# DAQ_Sch.net
KiCad netlist of a schematic drawn in Altium Designer
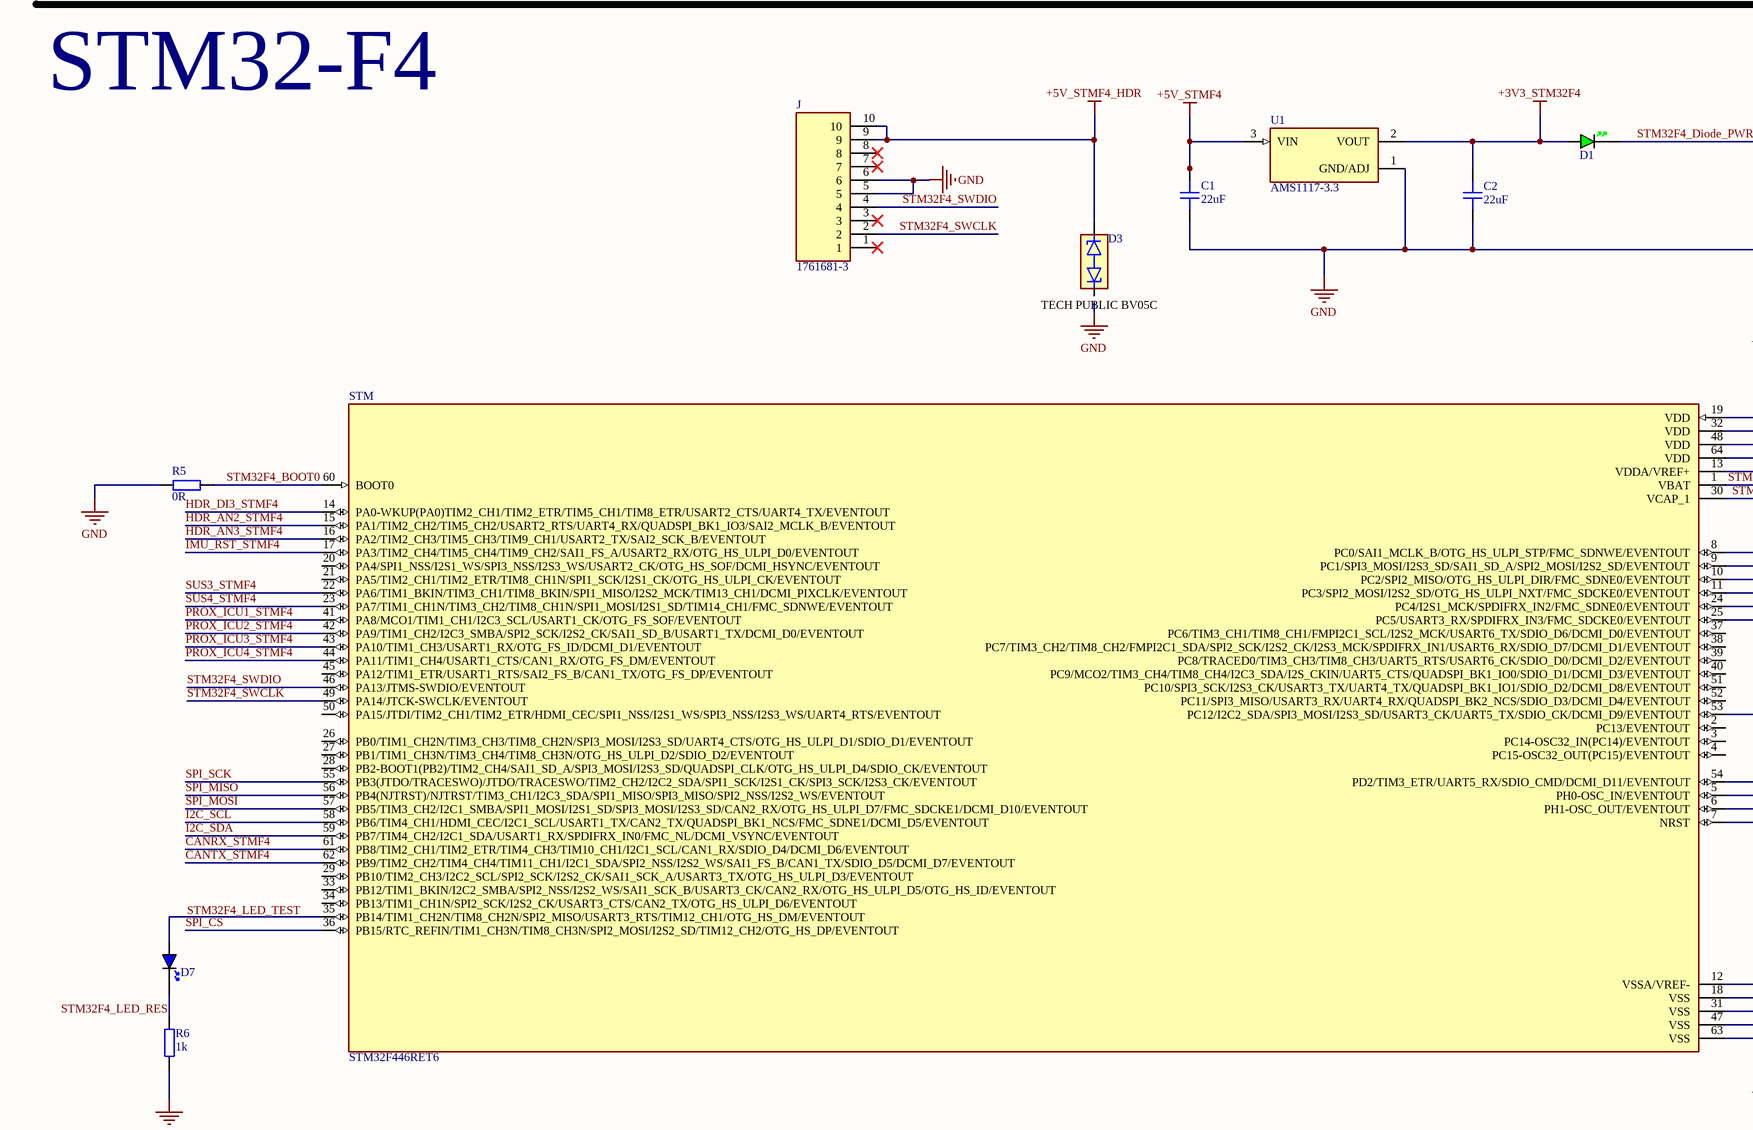
[diagram p0: DAQ_Sch.SchDoc, top left]
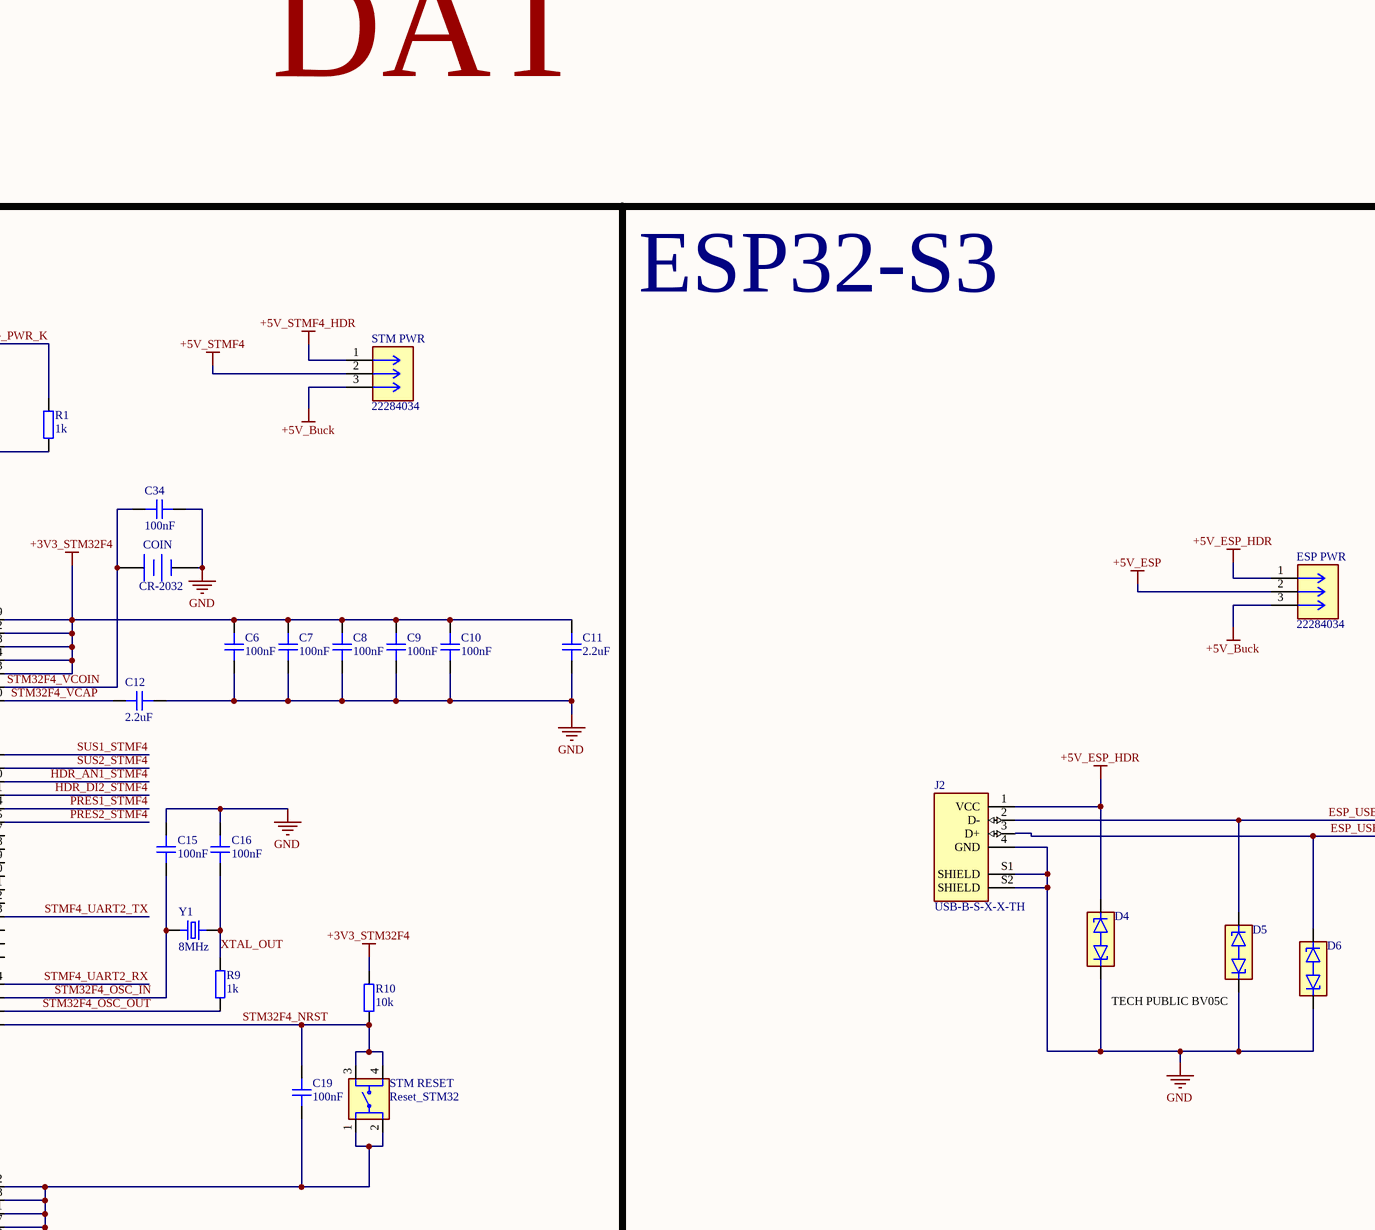
[diagram p1: DAQ_Sch.SchDoc, top middle]
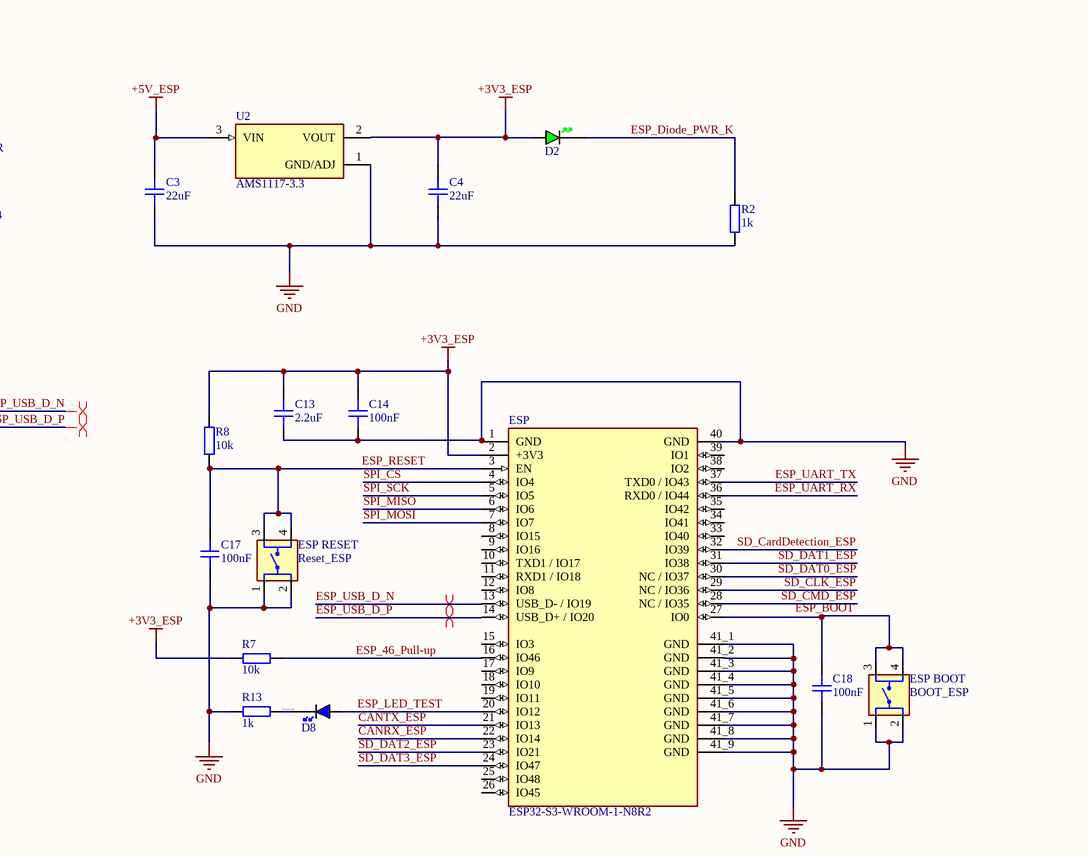
[diagram p2: DAQ_Sch.SchDoc, top right]
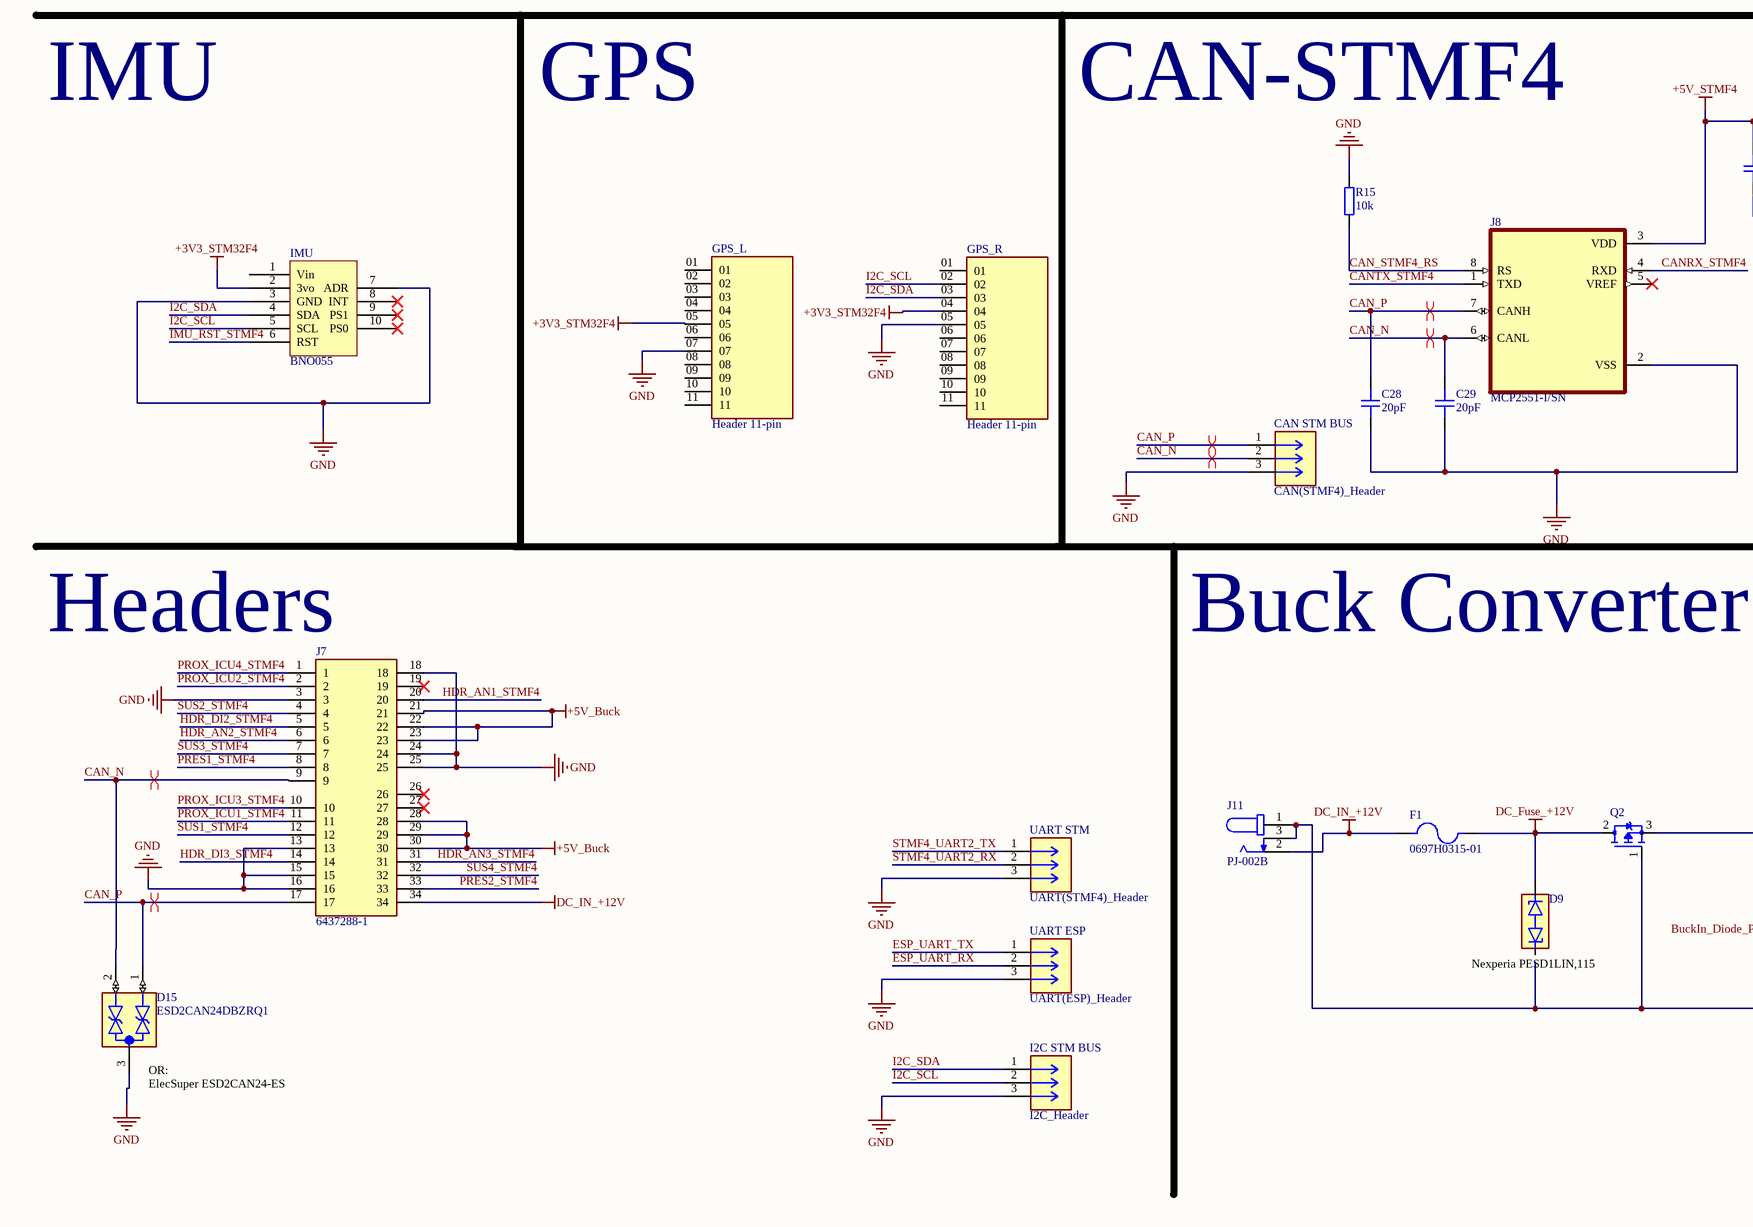
[diagram p3: DAQ_Sch.SchDoc, bottom left]
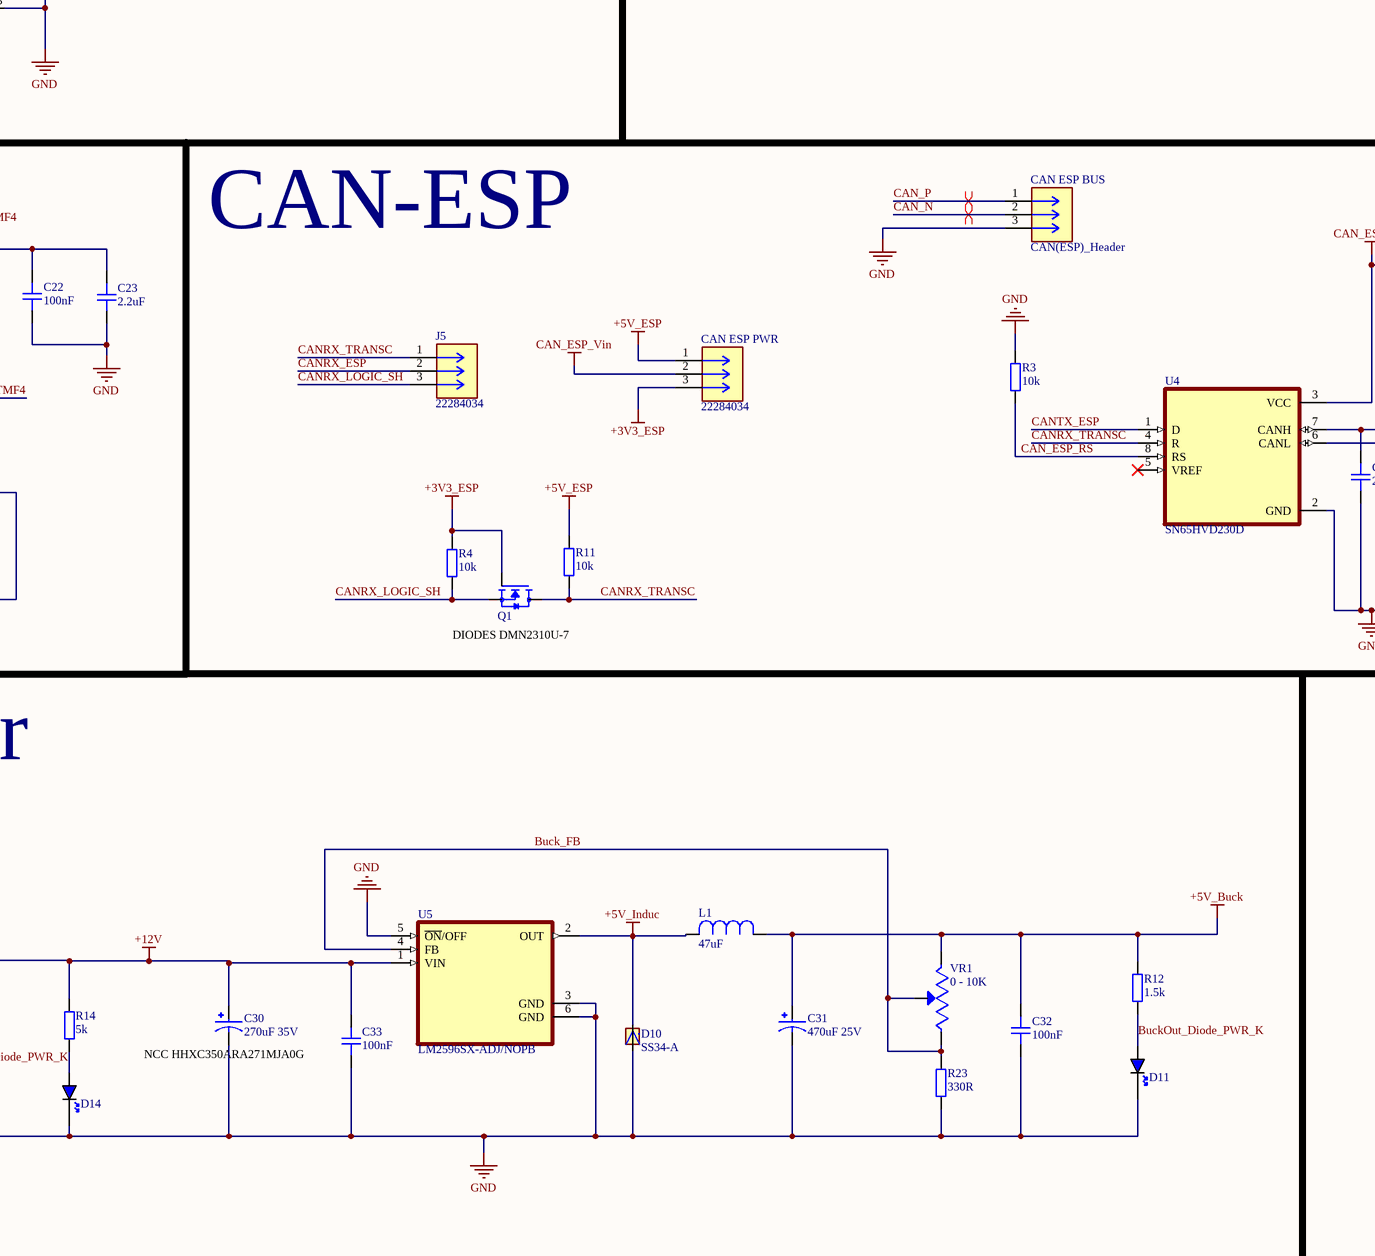
[diagram p4: DAQ_Sch.SchDoc, bottom middle]
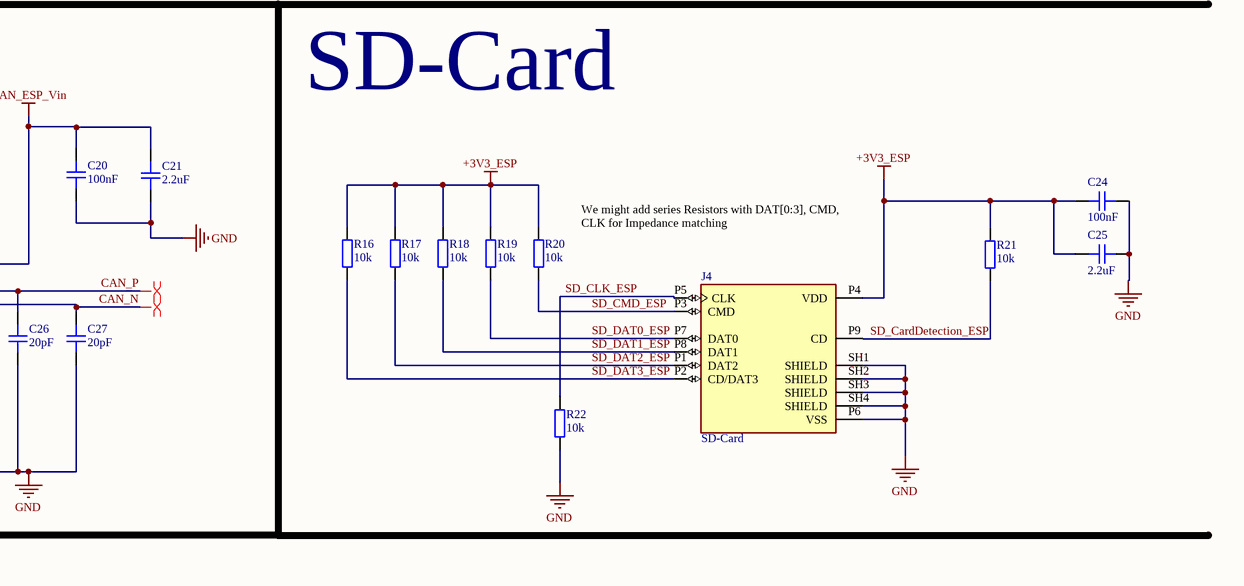
[diagram p5: DAQ_Sch.SchDoc, bottom right]

(export (version "E")
  (design (tool "Eeschema 10.0.6"))
  (components
    (comp (ref "C1")
      (value "22uF")
      (footprint "CAP_0805")
      (description "Capacitor SMD 0805")
      (libsource (lib "Schematic-Lib-PhilsLab") (part "CAP_0805"))
    )
    (comp (ref "C2")
      (value "22uF")
      (footprint "CAP_0805")
      (description "Capacitor SMD 0805")
      (libsource (lib "Schematic-Lib-PhilsLab") (part "CAP_0805"))
    )
    (comp (ref "C3")
      (value "22uF")
      (footprint "CAP_0805")
      (description "Capacitor SMD 0805")
      (libsource (lib "Schematic-Lib-PhilsLab") (part "CAP_0805"))
    )
    (comp (ref "C4")
      (value "22uF")
      (footprint "CAP_0805")
      (description "Capacitor SMD 0805")
      (libsource (lib "Schematic-Lib-PhilsLab") (part "CAP_0805"))
    )
    (comp (ref "C6")
      (value "100nF")
      (footprint "CAP_0805")
      (description "Capacitor SMD 0805")
      (libsource (lib "Schematic-Lib-PhilsLab") (part "CAP_0805"))
    )
    (comp (ref "C7")
      (value "100nF")
      (footprint "CAP_0805")
      (description "Capacitor SMD 0805")
      (libsource (lib "Schematic-Lib-PhilsLab") (part "CAP_0805"))
    )
    (comp (ref "C8")
      (value "100nF")
      (footprint "CAP_0805")
      (description "Capacitor SMD 0805")
      (libsource (lib "Schematic-Lib-PhilsLab") (part "CAP_0805"))
    )
    (comp (ref "C9")
      (value "100nF")
      (footprint "CAP_0805")
      (description "Capacitor SMD 0805")
      (libsource (lib "Schematic-Lib-PhilsLab") (part "CAP_0805"))
    )
    (comp (ref "C10")
      (value "100nF")
      (footprint "CAP_0805")
      (description "Capacitor SMD 0805")
      (libsource (lib "Schematic-Lib-PhilsLab") (part "CAP_0805"))
    )
    (comp (ref "C11")
      (value "2.2uF")
      (footprint "CAP_0805")
      (description "Capacitor SMD 0805")
      (libsource (lib "Schematic-Lib-PhilsLab") (part "CAP_0805"))
    )
    (comp (ref "C12")
      (value "2.2uF")
      (footprint "CAP_0805")
      (description "Capacitor SMD 0805")
      (libsource (lib "Schematic-Lib-PhilsLab") (part "CAP_0805"))
    )
    (comp (ref "C13")
      (value "2.2uF")
      (footprint "CAP_0805")
      (description "Capacitor SMD 0805")
      (libsource (lib "Schematic-Lib-PhilsLab") (part "CAP_0805"))
    )
    (comp (ref "C14")
      (value "100nF")
      (footprint "CAP_0805")
      (description "Capacitor SMD 0805")
      (libsource (lib "Schematic-Lib-PhilsLab") (part "CAP_0805"))
    )
    (comp (ref "C15")
      (value "100nF")
      (footprint "CAP_0805")
      (description "Capacitor SMD 0805")
      (libsource (lib "Schematic-Lib-PhilsLab") (part "CAP_0805"))
    )
    (comp (ref "C16")
      (value "100nF")
      (footprint "CAP_0805")
      (description "Capacitor SMD 0805")
      (libsource (lib "Schematic-Lib-PhilsLab") (part "CAP_0805"))
    )
    (comp (ref "C17")
      (value "100nF")
      (footprint "CAP_0805")
      (description "Capacitor SMD 0805")
      (libsource (lib "Schematic-Lib-PhilsLab") (part "CAP_0805"))
    )
    (comp (ref "C18")
      (value "100nF")
      (footprint "CAP_0805")
      (description "Capacitor SMD 0805")
      (libsource (lib "Schematic-Lib-PhilsLab") (part "CAP_0805"))
    )
    (comp (ref "C19")
      (value "100nF")
      (footprint "CAP_0805")
      (description "Capacitor SMD 0805")
      (libsource (lib "Schematic-Lib-PhilsLab") (part "CAP_0805"))
    )
    (comp (ref "C20")
      (value "100nF")
      (footprint "CAP_0805")
      (description "Capacitor SMD 0805")
      (libsource (lib "Schematic-Lib-PhilsLab") (part "CAP_0805"))
    )
    (comp (ref "C21")
      (value "2.2uF")
      (footprint "CAP_0805")
      (description "Capacitor SMD 0805")
      (libsource (lib "Schematic-Lib-PhilsLab") (part "CAP_0805"))
    )
    (comp (ref "C22")
      (value "100nF")
      (footprint "CAP_0805")
      (description "Capacitor SMD 0805")
      (libsource (lib "Schematic-Lib-PhilsLab") (part "CAP_0805"))
    )
    (comp (ref "C23")
      (value "2.2uF")
      (footprint "CAP_0805")
      (description "Capacitor SMD 0805")
      (libsource (lib "Schematic-Lib-PhilsLab") (part "CAP_0805"))
    )
    (comp (ref "C24")
      (value "100nF")
      (footprint "CAP_0805")
      (description "Capacitor SMD 0805")
      (libsource (lib "Schematic-Lib-PhilsLab") (part "CAP_0805"))
    )
    (comp (ref "C25")
      (value "2.2uF")
      (footprint "CAP_0805")
      (description "Capacitor SMD 0805")
      (libsource (lib "Schematic-Lib-PhilsLab") (part "CAP_0805"))
    )
    (comp (ref "C26")
      (value "20pF")
      (footprint "CAP_0805")
      (description "Capacitor SMD 0805")
      (libsource (lib "Schematic-Lib-PhilsLab") (part "CAP_0805"))
    )
    (comp (ref "C27")
      (value "20pF")
      (footprint "CAP_0805")
      (description "Capacitor SMD 0805")
      (libsource (lib "Schematic-Lib-PhilsLab") (part "CAP_0805"))
    )
    (comp (ref "C28")
      (value "20pF")
      (footprint "CAP_0805")
      (description "Capacitor SMD 0805")
      (libsource (lib "Schematic-Lib-PhilsLab") (part "CAP_0805"))
    )
    (comp (ref "C29")
      (value "20pF")
      (footprint "CAP_0805")
      (description "Capacitor SMD 0805")
      (libsource (lib "Schematic-Lib-PhilsLab") (part "CAP_0805"))
    )
    (comp (ref "C30")
      (value "270uF 35V")
      (footprint "CAP_EEEFT1E471AP")
      (description "35V ±20% 270uF SMD,D10xL10mm Hybrid Aluminum Electrolytic Capacitors ROHS")
      (fields (field (name "MF") "Panasonic") (field (name "MP") "EEEFT1E471AP"))
      (libsource (lib "CAP_EEEFT1E471AP_Sch") (part "EEEFT1E471AP"))
    )
    (comp (ref "C31")
      (value "470uF 25V")
      (footprint "CAP_EEEFT1E471AP")
      (description "Cap Aluminum Lytic 470uF 25V 20% (8 X 10.2mm) SMD 0.08 Ohm 850mA 2000h 105C Automotive T/R")
      (fields (field (name "MF") "Panasonic") (field (name "MP") "EEEFT1E471AP"))
      (libsource (lib "CAP_EEEFT1E471AP_Sch") (part "EEEFT1E471AP"))
    )
    (comp (ref "C32")
      (value "100nF")
      (footprint "CAP_0805")
      (description "Capacitor SMD 0805")
      (libsource (lib "Schematic-Lib-PhilsLab") (part "CAP_0805"))
    )
    (comp (ref "C33")
      (value "100nF")
      (footprint "CAP_0805")
      (description "Capacitor SMD 0805")
      (libsource (lib "Schematic-Lib-PhilsLab") (part "CAP_0805"))
    )
    (comp (ref "C34")
      (value "100nF")
      (footprint "CAP_0805")
      (description "Capacitor SMD 0805")
      (libsource (lib "Schematic-Lib-PhilsLab") (part "CAP_0805"))
    )
    (comp (ref "CAN ESP BUS")
      (value "CAN(ESP)_Header")
      (footprint "CONN_SD-42375-001_M320_03_MOL")
      (fields (field (name "MP") "22284034"))
      (libsource (lib "3_pin_Header_Sch") (part "22284034"))
    )
    (comp (ref "CAN ESP PWR")
      (value "22284034")
      (footprint "CONN_SD-42375-001_M320_03_MOL")
      (libsource (lib "3_pin_Header_Sch") (part "22284034"))
    )
    (comp (ref "CAN STM BUS")
      (value "CAN(STMF4)_Header")
      (footprint "CONN_SD-42375-001_M320_03_MOL")
      (fields (field (name "MP") "22284034"))
      (libsource (lib "3_pin_Header_Sch") (part "22284034"))
    )
    (comp (ref "COIN")
      (value "CR-2032")
      (footprint "PANA-CR-2032HFN")
      (description "Coin Cell Battery, 225 mAh, 0.2 mA, 3 V, -30 to 60 degC, Bulk")
      (fields (field (name "MANUFACTURER") "Panasonic"))
      (libsource (lib "Altium Content Vault") (part "BATTERY_SINGLE-2"))
    )
    (comp (ref "D1")
      (value "GREEN")
      (footprint "LED_0805_GREEN")
      (description "LED 0805 GREEN SMD")
      (libsource (lib "Schematic-Lib-PhilsLab") (part "LED_0805_GREEN"))
    )
    (comp (ref "D2")
      (value "GREEN")
      (footprint "LED_0805_GREEN")
      (description "LED 0805 GREEN SMD")
      (libsource (lib "Schematic-Lib-PhilsLab") (part "LED_0805_GREEN"))
    )
    (comp (ref "D3")
      (value "5V-TVS")
      (footprint "DIO_PESD1LIN")
      (description "10A 8V Bidirectional 5V SOD-323 ESD and Surge Protection (TVS/ESD) ROHS")
      (fields (field (name "MF") "Nexperia USA") (field (name "MP") "PESD1LIN"))
      (libsource (lib "5V_TVS_Diode_Sch") (part "PESD1LIN"))
    )
    (comp (ref "D4")
      (value "5V-TVS")
      (footprint "DIO_PESD1LIN")
      (description "10A 8V Bidirectional 5V SOD-323 ESD and Surge Protection (TVS/ESD) ROHS")
      (fields (field (name "MF") "Nexperia USA") (field (name "MP") "PESD1LIN"))
      (libsource (lib "5V_TVS_Diode_Sch") (part "PESD1LIN"))
    )
    (comp (ref "D5")
      (value "5V-TVS")
      (footprint "DIO_PESD1LIN")
      (description "10A 8V Bidirectional 5V SOD-323 ESD and Surge Protection (TVS/ESD) ROHS")
      (fields (field (name "MF") "Nexperia USA") (field (name "MP") "PESD1LIN"))
      (libsource (lib "5V_TVS_Diode_Sch") (part "PESD1LIN"))
    )
    (comp (ref "D6")
      (value "5V-TVS")
      (footprint "DIO_PESD1LIN")
      (description "10A 8V Bidirectional 5V SOD-323 ESD and Surge Protection (TVS/ESD) ROHS")
      (fields (field (name "MF") "Nexperia USA") (field (name "MP") "PESD1LIN"))
      (libsource (lib "5V_TVS_Diode_Sch") (part "PESD1LIN"))
    )
    (comp (ref "D7")
      (value "BLUE")
      (footprint "LED_0805_BLUE")
      (description "LED 0805 BLUE SMD")
      (libsource (lib "Schematic-Lib-PhilsLab") (part "LED_0805_BLUE"))
    )
    (comp (ref "D8")
      (value "BLUE")
      (footprint "LED_0805_BLUE")
      (description "LED 0805 BLUE SMD")
      (libsource (lib "Schematic-Lib-PhilsLab") (part "LED_0805_BLUE"))
    )
    (comp (ref "D9")
      (value "5V-TVS")
      (footprint "DIO_PESD1LIN")
      (description "44V, 70V Clamp 3A (8/20Âµs) Ipp Tvs Diode Surface Mount SOD-323")
      (fields (field (name "MF") "Nexperia USA") (field (name "MP") "PESD1LIN"))
      (libsource (lib "5V_TVS_Diode_Sch") (part "PESD1LIN"))
    )
    (comp (ref "D10")
      (value "SS34-A")
      (footprint "DO-214AC")
      (description "Schottky barrier diode, 3A, 40V")
      (fields (field (name "MF") "hy electronic corp") (field (name "MP") "SS34A"))
      (libsource (lib "Buck_CatchDiode_SS34-A_Sch") (part "SS34-A"))
    )
    (comp (ref "D11")
      (value "BLUE")
      (footprint "LED_0805_BLUE")
      (description "LED 0805 BLUE SMD")
      (libsource (lib "Schematic-Lib-PhilsLab") (part "LED_0805_BLUE"))
    )
    (comp (ref "D14")
      (value "BLUE")
      (footprint "LED_0805_BLUE")
      (description "LED 0805 BLUE SMD")
      (libsource (lib "Schematic-Lib-PhilsLab") (part "LED_0805_BLUE"))
    )
    (comp (ref "D15")
      (value "ESD2CAN24DBZRQ1")
      (footprint "SOT95P237X112-3N")
      (description "Automotive, dual, 3-pF, ±24-V, ±30-kV ESD protection diode for in-vehicle networks")
      (fields (field (name "MF") "Texas Instruments"))
      (libsource (lib "ESD_CAN_Sch") (part "ESD2CAN24DBZRQ1"))
    )
    (comp (ref "ESP")
      (value "ESP32-S3-WROOM-1-N8R2")
      (footprint "ESP32-S3-WROOM-1_NO-KEEPOUT")
      (fields
        (field (name "MPN") "ESP32-S3-WROOM-1-N16R2")
        (field (name "MF") "Espressif Systems")
        (field (name "DIGI-KEY_PART_NUMBER") "1965-ESP32-S3-WROOM-1-N16R2TR-ND")
      )
      (libsource (lib "ESP32-S3-WROOM-1") (part "ESP32-S3-WROOM-1"))
    )
    (comp (ref "ESP BOOT")
      (value "BOOT_ESP")
      (footprint "SW_FSM8JH")
      (description "Tactile Switch SPST-NO Top Actuated Through Hole")
      (fields (field (name "MP") "FSM8JH") (field (name "MF") "TE Connectivity"))
      (libsource (lib "Button_Sch") (part "FSM8JH"))
    )
    (comp (ref "ESP PWR")
      (value "22284034")
      (footprint "CONN_SD-42375-001_M320_03_MOL")
      (libsource (lib "3_pin_Header_Sch") (part "22284034"))
    )
    (comp (ref "ESP RESET")
      (value "Reset_ESP")
      (footprint "SW_FSM8JH")
      (description "Tactile Switch SPST-NO Top Actuated Through Hole")
      (fields (field (name "MP") "FSM8JH") (field (name "MF") "TE Connectivity"))
      (libsource (lib "Button_Sch") (part "FSM8JH"))
    )
    (comp (ref "F1")
      (value "0697H0315-01")
      (footprint "FUSRR508W60L835T400H810")
      (description "2-Pin Radial Fuse ¦ Rectangular ¦ Slow Blow ¦ UL ¦ 315mA")
      (fields (field (name "MF") "Bel Fuse"))
      (libsource (lib "Radial_Fuse_Sch") (part "0697H0315-01"))
    )
    (comp (ref "GPS_L")
      (value "Header 11-pin")
      (footprint "SAMTEC_MTSW-111-22-T-S-440")
      (fields (field (name "MP") "MTSW-111-22-T-S-440"))
      (libsource (lib "11-pin_Header_Sch") (part "MTSW-111-22-T-S-440"))
    )
    (comp (ref "GPS_R")
      (value "Header 11-pin")
      (footprint "SAMTEC_MTSW-111-22-T-S-440")
      (fields (field (name "MP") "MTSW-111-22-T-S-440"))
      (libsource (lib "11-pin_Header_Sch") (part "MTSW-111-22-T-S-440"))
    )
    (comp (ref "I2C STM BUS")
      (value "I2C_Header")
      (footprint "CONN_SD-42375-001_M320_03_MOL")
      (fields (field (name "MP") "22284034"))
      (libsource (lib "3_pin_Header_Sch") (part "22284034"))
    )
    (comp (ref "IMU") (value "BNO055") (footprint "IMU") (libsource (lib "BNO055") (part "Component_1")))
    (comp (ref "J")
      (value "1761681-3")
      (footprint "TE_1761681-3")
      (description "Conn Shrouded Header HDR 10 POS 2.54mm Solder ST Thru-Hole Tray")
      (fields (field (name "MF") "TE Connectivity"))
      (libsource (lib "10_pin_Box_Header_Sch") (part "1761681-3"))
    )
    (comp (ref "J2")
      (value "USB-B-S-X-X-TH")
      (footprint "SAMTEC_USB-B-S-X-X-TH")
      (description "USB-B (USB TYPE-B) USB 2.0 Receptacle Connector 4 Position Through Hole, Right Angle")
      (fields (field (name "MF") "Samtec") (field (name "MP") "USB-B-S-F-W-TH-TR"))
      (libsource (lib "USB-B_Connector_Sch") (part "USB-B-S-X-X-TH"))
    )
    (comp (ref "J4")
      (value "SD-Card")
      (footprint "GCT_MEM2075-00-140-01-A")
      (description "9 (8 + 1) Position Card Connector microSD Surface Mount, Right Angle Gold")
      (fields (field (name "MF") "Global Connector Technology") (field (name "MP") "MEM2075-00-140-01-A"))
      (libsource (lib "SD-Card_Reader_Sch") (part "MEM2075-00-140-01-A"))
    )
    (comp (ref "J5")
      (value "22284034")
      (footprint "CONN_SD-42375-001_M320_03_MOL")
      (libsource (lib "3_pin_Header_Sch") (part "22284034"))
    )
    (comp (ref "J7")
      (value "6437288-1")
      (footprint "TE_6437288-1")
      (fields (field (name "MF") "TE Connectivity"))
      (libsource (lib "34-pin_Connector_Sch") (part "6437288-1"))
    )
    (comp (ref "J8")
      (value "MCP2551-I/SN")
      (footprint "MCP2551-I_SN_Pcb:SOIC127P599X175-8N")
      (libsource (lib "MCP2551-I_SN_Sch") (part "MCP2551-I/SN"))
    )
    (comp (ref "J11")
      (value "PJ-002B")
      (footprint "CUI_PJ-002B")
      (description "2.5 x 6.5 mm, 2.5 A, Horizontal, Through Hole, Dc Power Jack Connector")
      (fields (field (name "MF") "Same Sky"))
      (libsource (lib "DC_Barrel_Jack_Sch") (part "PJ-002B"))
    )
    (comp (ref "L1")
      (value "47uF")
      (footprint "IND_CDRH127/LDNP-470MC_SUM")
      (description "Inductor Power Shielded Drum Core 47uH 20% 1KHz Ferrite 4.1A 0.078Ohm DCR T/R")
      (fields (field (name "MF") "Sumida Corporation") (field (name "MP") "CDRH127/LDNP-470MC"))
      (libsource (lib "CDRH127_LDNP-470MC") (part "CDRH127/LDNP-470MC"))
    )
    (comp (ref "Q1")
      (value "2N7002")
      (footprint "TRANS_2N7002")
      (description "MOSFET, SOT-23, N, 60V, 0.28A, 5â„¦, 150Â°C")
      (fields (field (name "MF") "Diotec Semiconductor"))
      (libsource (lib "N-MOSFET_SOT23_Sch") (part "2N7002"))
    )
    (comp (ref "Q2")
      (value "IRF4905STRRPBF")
      (footprint "TRANS_IRF4905STRRPBF")
      (fields (field (name "MF") "Infineon Technologies"))
      (libsource (lib "P-MOSFIT_IRF4905STRRPBF_Sch") (part "IRF4905STRRPBF"))
    )
    (comp (ref "R1")
      (value "1k")
      (footprint "RES_0805")
      (description "Resistor SMD 0805")
      (libsource (lib "Schematic-Lib-PhilsLab") (part "RES_0805"))
    )
    (comp (ref "R2")
      (value "1k")
      (footprint "RES_0805")
      (description "Resistor SMD 0805")
      (libsource (lib "Schematic-Lib-PhilsLab") (part "RES_0805"))
    )
    (comp (ref "R3")
      (value "10k")
      (footprint "RES_0805")
      (description "Resistor SMD 0805")
      (libsource (lib "Schematic-Lib-PhilsLab") (part "RES_0805"))
    )
    (comp (ref "R4")
      (value "10k")
      (footprint "RES_0805")
      (description "Resistor SMD 0805")
      (libsource (lib "Schematic-Lib-PhilsLab") (part "RES_0805"))
    )
    (comp (ref "R5")
      (value "0R")
      (footprint "RES_0805")
      (description "Resistor SMD 0805")
      (libsource (lib "Schematic-Lib-PhilsLab") (part "RES_0805"))
    )
    (comp (ref "R6")
      (value "1k")
      (footprint "RES_0805")
      (description "Resistor SMD 0805")
      (libsource (lib "Schematic-Lib-PhilsLab") (part "RES_0805"))
    )
    (comp (ref "R7")
      (value "10k")
      (footprint "RES_0805")
      (description "Resistor SMD 0805")
      (libsource (lib "Schematic-Lib-PhilsLab") (part "RES_0805"))
    )
    (comp (ref "R8")
      (value "10k")
      (footprint "RES_0805")
      (description "Resistor SMD 0805")
      (libsource (lib "Schematic-Lib-PhilsLab") (part "RES_0805"))
    )
    (comp (ref "R9")
      (value "1k")
      (footprint "RES_0805")
      (description "Resistor SMD 0805")
      (libsource (lib "Schematic-Lib-PhilsLab") (part "RES_0805"))
    )
    (comp (ref "R10")
      (value "10k")
      (footprint "RES_0805")
      (description "Resistor SMD 0805")
      (libsource (lib "Schematic-Lib-PhilsLab") (part "RES_0805"))
    )
    (comp (ref "R11")
      (value "10k")
      (footprint "RES_0805")
      (description "Resistor SMD 0805")
      (libsource (lib "Schematic-Lib-PhilsLab") (part "RES_0805"))
    )
    (comp (ref "R12")
      (value "1.5k")
      (footprint "RES_0805")
      (description "Resistor SMD 0805")
      (libsource (lib "Schematic-Lib-PhilsLab") (part "RES_0805"))
    )
    (comp (ref "R13")
      (value "1k")
      (footprint "RES_0805")
      (description "Resistor SMD 0805")
      (libsource (lib "Schematic-Lib-PhilsLab") (part "RES_0805"))
    )
    (comp (ref "R14")
      (value "5k")
      (footprint "RES_0805")
      (description "Resistor SMD 0805")
      (libsource (lib "Schematic-Lib-PhilsLab") (part "RES_0805"))
    )
    (comp (ref "R15")
      (value "10k")
      (footprint "RES_0805")
      (description "Resistor SMD 0805")
      (libsource (lib "Schematic-Lib-PhilsLab") (part "RES_0805"))
    )
    (comp (ref "R16")
      (value "10k")
      (footprint "RES_0805")
      (description "Resistor SMD 0805")
      (libsource (lib "Schematic-Lib-PhilsLab") (part "RES_0805"))
    )
    (comp (ref "R17")
      (value "10k")
      (footprint "RES_0805")
      (description "Resistor SMD 0805")
      (libsource (lib "Schematic-Lib-PhilsLab") (part "RES_0805"))
    )
    (comp (ref "R18")
      (value "10k")
      (footprint "RES_0805")
      (description "Resistor SMD 0805")
      (libsource (lib "Schematic-Lib-PhilsLab") (part "RES_0805"))
    )
    (comp (ref "R19")
      (value "10k")
      (footprint "RES_0805")
      (description "Resistor SMD 0805")
      (libsource (lib "Schematic-Lib-PhilsLab") (part "RES_0805"))
    )
    (comp (ref "R20")
      (value "10k")
      (footprint "RES_0805")
      (description "Resistor SMD 0805")
      (libsource (lib "Schematic-Lib-PhilsLab") (part "RES_0805"))
    )
    (comp (ref "R21")
      (value "10k")
      (footprint "RES_0805")
      (description "Resistor SMD 0805")
      (libsource (lib "Schematic-Lib-PhilsLab") (part "RES_0805"))
    )
    (comp (ref "R22")
      (value "10k")
      (footprint "RES_0805")
      (description "Resistor SMD 0805")
      (libsource (lib "Schematic-Lib-PhilsLab") (part "RES_0805"))
    )
    (comp (ref "R23")
      (value "330R")
      (footprint "RES_0805")
      (description "Resistor SMD 0805")
      (libsource (lib "Schematic-Lib-PhilsLab") (part "RES_0805"))
    )
    (comp (ref "STM")
      (value "STM32F446RET6")
      (footprint "QFP50P1200X1200X160-64N")
      (description "ARMÂ® CortexÂ®-M4 STM32F4 Microcontroller IC 32-Bit 180MHz 512KB _512K x 8_ FLASH 64-LQFP _10x10_")
      (fields (field (name "MF") "STMicroelectronics"))
      (libsource (lib "STM32F4_Sch") (part "STM32F446RET6"))
    )
    (comp (ref "STM PWR")
      (value "22284034")
      (footprint "CONN_SD-42375-001_M320_03_MOL")
      (libsource (lib "3_pin_Header_Sch") (part "22284034"))
    )
    (comp (ref "STM RESET")
      (value "Reset_STM32")
      (footprint "SW_FSM8JH")
      (description "Tactile Switch SPST-NO Top Actuated Through Hole")
      (fields (field (name "MP") "FSM8JH") (field (name "MF") "TE Connectivity"))
      (libsource (lib "Button_Sch") (part "FSM8JH"))
    )
    (comp (ref "U1")
      (value "AMS1117-3.3")
      (footprint "SOT229P700X180-4N")
      (description "Sot223/Pkg 1-Amp 3.3-Volt Low Drop Out Voltage Regulatator")
      (fields (field (name "MF") "Advanced Monolithic Systems"))
      (libsource (lib "AMS1117-3.3_Sch") (part "AMS1117-3.3"))
    )
    (comp (ref "U2")
      (value "AMS1117-3.3")
      (footprint "SOT229P700X180-4N")
      (description "Sot223/Pkg 1-Amp 3.3-Volt Low Drop Out Voltage Regulatator")
      (fields (field (name "MF") "Advanced Monolithic Systems"))
      (libsource (lib "AMS1117-3.3_Sch") (part "AMS1117-3.3"))
    )
    (comp (ref "U4")
      (value "SN65HVD230D")
      (footprint "SOIC127P599X175-8N")
      (description "3.3 V CAN Transceiver with Standby Mode")
      (fields (field (name "MF") "Texas Instruments"))
      (libsource (lib "SN65HVD230D_CAN3.3V_Sch") (part "SN65HVD230D"))
    )
    (comp (ref "U5")
      (value "LM2596SX-ADJ/NOPB")
      (footprint "VREG_LM2596SX-ADJ/NOPB")
      (fields (field (name "MF") "Texas Instruments"))
      (libsource (lib "LM2596SX-ADJ_NOPB_Sch") (part "LM2596SX-ADJ/NOPB"))
    )
    (comp (ref "UART ESP")
      (value "UART(ESP)_Header")
      (footprint "CONN_SD-42375-001_M320_03_MOL")
      (fields (field (name "MP") "22284034"))
      (libsource (lib "3_pin_Header_Sch") (part "22284034"))
    )
    (comp (ref "UART STM")
      (value "UART(STMF4)_Header")
      (footprint "CONN_SD-42375-001_M320_03_MOL")
      (fields (field (name "MP") "22284034"))
      (libsource (lib "3_pin_Header_Sch") (part "22284034"))
    )
    (comp (ref "VR1")
      (value "0 - 10K")
      (footprint "TRIM_3296W-1-103LF")
      (description "Trimmer, Cermet, Rest 10 Kilohms, PCB, 25 Turns, Pwr-Rtg 0.5W, 3296 Series ¦ Bourns 3296W-1-103LF")
      (fields (field (name "MF") "Bourns") (field (name "MP") "3296W-1-103LF"))
      (libsource (lib "Pot_10KOhm_Sch") (part "3296W-1-103LF"))
    )
    (comp (ref "Y1")
      (value "8MHz")
      (footprint "XTAL_ECS-80-20-5PVX")
      (description "SMD Quartz crystal")
      (fields (field (name "MP") "ECS-80-20-5PVX"))
      (libsource (lib "Crystal_8MHz_20pF_Sch") (part "ECS-80-20-5PVX"))
    )
  )
  (nets
    (net (code "1") (name "+3V3_ESP") (class "Default")
      (node (ref "C13") (pin "1") (pinfunction "1_1") (pintype "passive"))
      (node (ref "C14") (pin "1") (pinfunction "1_1") (pintype "passive"))
      (node (ref "C24") (pin "2") (pinfunction "2_2") (pintype "passive"))
      (node (ref "C25") (pin "2") (pinfunction "2_2") (pintype "passive"))
      (node (ref "C4") (pin "2") (pinfunction "2_2") (pintype "passive"))
      (node (ref "CAN ESP PWR") (pin "3") (pinfunction "3_3") (pintype "passive"))
      (node (ref "D2") (pin "A") (pinfunction "A_A") (pintype "passive"))
      (node (ref "ESP") (pin "2") (pinfunction "+3V3_2") (pintype "power_in"))
      (node (ref "J4") (pin "P4") (pinfunction "VDD_P4") (pintype "power_in"))
      (node (ref "Q1") (pin "1") (pinfunction "G_1") (pintype "passive"))
      (node (ref "R16") (pin "2") (pinfunction "2_2") (pintype "passive"))
      (node (ref "R17") (pin "2") (pinfunction "2_2") (pintype "passive"))
      (node (ref "R18") (pin "2") (pinfunction "2_2") (pintype "passive"))
      (node (ref "R19") (pin "2") (pinfunction "2_2") (pintype "passive"))
      (node (ref "R20") (pin "2") (pinfunction "2_2") (pintype "passive"))
      (node (ref "R21") (pin "2") (pinfunction "2_2") (pintype "passive"))
      (node (ref "R4") (pin "2") (pinfunction "2_2") (pintype "passive"))
      (node (ref "R7") (pin "1") (pinfunction "1_1") (pintype "passive"))
      (node (ref "R8") (pin "2") (pinfunction "2_2") (pintype "passive"))
      (node (ref "U2") (pin "2") (pinfunction "VOUT_2") (pintype "power_in"))
    )
    (net (code "2") (name "+3V3_STM32F4") (class "Default")
      (node (ref "C10") (pin "2") (pinfunction "2_2") (pintype "passive"))
      (node (ref "C11") (pin "2") (pinfunction "2_2") (pintype "passive"))
      (node (ref "C2") (pin "2") (pinfunction "2_2") (pintype "passive"))
      (node (ref "C6") (pin "2") (pinfunction "2_2") (pintype "passive"))
      (node (ref "C7") (pin "2") (pinfunction "2_2") (pintype "passive"))
      (node (ref "C8") (pin "2") (pinfunction "2_2") (pintype "passive"))
      (node (ref "C9") (pin "2") (pinfunction "2_2") (pintype "passive"))
      (node (ref "D1") (pin "A") (pinfunction "A_A") (pintype "passive"))
      (node (ref "GPS_L") (pin "05") (pinfunction "05_05") (pintype "passive"))
      (node (ref "GPS_R") (pin "04") (pinfunction "04_04") (pintype "passive"))
      (node (ref "IMU") (pin "2") (pinfunction "3vo_2") (pintype "passive"))
      (node (ref "R10") (pin "2") (pinfunction "2_2") (pintype "passive"))
      (node (ref "STM") (pin "13") (pinfunction "VDDA/VREF+_13") (pintype "power_in"))
      (node (ref "STM") (pin "19") (pinfunction "VDD_19") (pintype "input"))
      (node (ref "STM") (pin "32") (pinfunction "VDD_32") (pintype "power_in"))
      (node (ref "STM") (pin "48") (pinfunction "VDD_48") (pintype "power_in"))
      (node (ref "STM") (pin "64") (pinfunction "VDD_64") (pintype "power_in"))
      (node (ref "U1") (pin "2") (pinfunction "VOUT_2") (pintype "power_in"))
    )
    (net (code "3") (name "+5V_Buck") (class "Default")
      (node (ref "C31") (pin "1") (pinfunction "1_1") (pintype "passive"))
      (node (ref "C32") (pin "2") (pinfunction "2_2") (pintype "passive"))
      (node (ref "ESP PWR") (pin "3") (pinfunction "3_3") (pintype "passive"))
      (node (ref "J7") (pin "21") (pinfunction "21_21") (pintype "passive"))
      (node (ref "J7") (pin "22") (pinfunction "22_22") (pintype "passive"))
      (node (ref "J7") (pin "23") (pinfunction "23_23") (pintype "passive"))
      (node (ref "J7") (pin "28") (pinfunction "28_28") (pintype "passive"))
      (node (ref "J7") (pin "29") (pinfunction "29_29") (pintype "passive"))
      (node (ref "J7") (pin "30") (pinfunction "30_30") (pintype "passive"))
      (node (ref "L1") (pin "1") (pinfunction "1_1") (pintype "passive"))
      (node (ref "R12") (pin "2") (pinfunction "2_2") (pintype "passive"))
      (node (ref "STM PWR") (pin "3") (pinfunction "3_3") (pintype "passive"))
      (node (ref "VR1") (pin "3") (pinfunction "CW_3") (pintype "passive"))
    )
    (net (code "4") (name "+5V_ESP") (class "Default")
      (node (ref "C3") (pin "2") (pinfunction "2_2") (pintype "passive"))
      (node (ref "CAN ESP PWR") (pin "1") (pinfunction "1_1") (pintype "passive"))
      (node (ref "ESP PWR") (pin "2") (pinfunction "2_2") (pintype "passive"))
      (node (ref "R11") (pin "2") (pinfunction "2_2") (pintype "passive"))
      (node (ref "U2") (pin "3") (pinfunction "VIN_3") (pintype "input"))
    )
    (net (code "5") (name "+5V_ESP_HDR") (class "Default")
      (node (ref "D4") (pin "2") (pinfunction "2_2") (pintype "passive"))
      (node (ref "ESP PWR") (pin "1") (pinfunction "1_1") (pintype "passive"))
      (node (ref "J2") (pin "1") (pinfunction "VCC_1") (pintype "power_in"))
    )
    (net (code "6") (name "+5V_Induc") (class "Default")
      (node (ref "D10") (pin "C") (pinfunction "C_C") (pintype "passive"))
      (node (ref "L1") (pin "2") (pinfunction "2_2") (pintype "passive"))
      (node (ref "U5") (pin "2") (pinfunction "OUT_2") (pintype "output"))
    )
    (net (code "7") (name "+5V_STMF4") (class "Default")
      (node (ref "C1") (pin "2") (pinfunction "2_2") (pintype "passive"))
      (node (ref "C22") (pin "2") (pinfunction "2_2") (pintype "passive"))
      (node (ref "C23") (pin "2") (pinfunction "2_2") (pintype "passive"))
      (node (ref "J8") (pin "3") (pinfunction "VDD_3") (pintype "power_in"))
      (node (ref "STM PWR") (pin "2") (pinfunction "2_2") (pintype "passive"))
      (node (ref "U1") (pin "3") (pinfunction "VIN_3") (pintype "input"))
    )
    (net (code "8") (name "+5V_STMF4_HDR") (class "Default")
      (node (ref "D3") (pin "2") (pinfunction "2_2") (pintype "passive"))
      (node (ref "J") (pin "10") (pinfunction "10_10") (pintype "passive"))
      (node (ref "J") (pin "9") (pinfunction "9_9") (pintype "passive"))
      (node (ref "STM PWR") (pin "1") (pinfunction "1_1") (pintype "passive"))
    )
    (net (code "9") (name "+12V") (class "Default")
      (node (ref "C30") (pin "1") (pinfunction "1_1") (pintype "passive"))
      (node (ref "C33") (pin "2") (pinfunction "2_2") (pintype "passive"))
      (node (ref "Q2") (pin "3") (pinfunction "S_3") (pintype "passive"))
      (node (ref "R14") (pin "2") (pinfunction "2_2") (pintype "passive"))
      (node (ref "U5") (pin "1") (pinfunction "VIN_1") (pintype "input"))
    )
    (net (code "10") (name "/BuckIn_Diode_PWR_K") (class "Default")
      (node (ref "D14") (pin "A") (pinfunction "A_A") (pintype "passive"))
      (node (ref "R14") (pin "1") (pinfunction "1_1") (pintype "passive"))
    )
    (net (code "11") (name "/BuckOut_Diode_PWR_K") (class "Default")
      (node (ref "D11") (pin "A") (pinfunction "A_A") (pintype "passive"))
      (node (ref "R12") (pin "1") (pinfunction "1_1") (pintype "passive"))
    )
    (net (code "12") (name "/Buck_FB") (class "Default")
      (node (ref "R23") (pin "2") (pinfunction "2_2") (pintype "passive"))
      (node (ref "U5") (pin "4") (pinfunction "FB_4") (pintype "input"))
      (node (ref "VR1") (pin "1") (pinfunction "CCW_1") (pintype "passive"))
      (node (ref "VR1") (pin "2") (pinfunction "WIPER_2") (pintype "passive"))
    )
    (net (code "13") (name "/CANRX_ESP") (class "Default")
      (node (ref "ESP") (pin "22") (pinfunction "IO14_22") (pintype "bidirectional"))
      (node (ref "J5") (pin "2") (pinfunction "2_2") (pintype "passive"))
    )
    (net (code "14") (name "/CANRX_LOGIC_SH") (class "Default")
      (node (ref "J5") (pin "3") (pinfunction "3_3") (pintype "passive"))
      (node (ref "Q1") (pin "2") (pinfunction "S_2") (pintype "passive"))
      (node (ref "R4") (pin "1") (pinfunction "1_1") (pintype "passive"))
    )
    (net (code "15") (name "/CANRX_STMF4") (class "Default")
      (node (ref "J8") (pin "4") (pinfunction "RXD_4") (pintype "input"))
      (node (ref "STM") (pin "61") (pinfunction "PB8/TIM2_CH1/TIM2_ETR/TIM4_CH3/TIM10_CH1/I2C1_SCL/CAN1_RX/SDIO_D4/DCMI_D6/EVENTOUT_61") (pintype "bidirectional"))
    )
    (net (code "16") (name "/CANRX_TRANSC") (class "Default")
      (node (ref "J5") (pin "1") (pinfunction "1_1") (pintype "passive"))
      (node (ref "Q1") (pin "3") (pinfunction "D_3") (pintype "passive"))
      (node (ref "R11") (pin "1") (pinfunction "1_1") (pintype "passive"))
      (node (ref "U4") (pin "4") (pinfunction "R_4") (pintype "input"))
    )
    (net (code "17") (name "/CANTX_ESP") (class "Default")
      (node (ref "ESP") (pin "21") (pinfunction "IO13_21") (pintype "bidirectional"))
      (node (ref "U4") (pin "1") (pinfunction "D_1") (pintype "input"))
    )
    (net (code "18") (name "/CANTX_STMF4") (class "Default")
      (node (ref "J8") (pin "1") (pinfunction "TXD_1") (pintype "input"))
      (node (ref "STM") (pin "62") (pinfunction "PB9/TIM2_CH2/TIM4_CH4/TIM11_CH1/I2C1_SDA/SPI2_NSS/I2S2_WS/SAI1_FS_B/CAN1_TX/SDIO_D5/DCMI_D7/EVENTOUT_62") (pintype "bidirectional"))
    )
    (net (code "19") (name "/CAN_ESP_RS") (class "Default")
      (node (ref "R3") (pin "1") (pinfunction "1_1") (pintype "passive"))
      (node (ref "U4") (pin "8") (pinfunction "RS_8") (pintype "input"))
    )
    (net (code "20") (name "/CAN_N") (class "Default")
      (node (ref "C27") (pin "2") (pinfunction "2_2") (pintype "passive"))
      (node (ref "C29") (pin "2") (pinfunction "2_2") (pintype "passive"))
      (node (ref "CAN ESP BUS") (pin "2") (pinfunction "2_2") (pintype "passive"))
      (node (ref "CAN STM BUS") (pin "2") (pinfunction "2_2") (pintype "passive"))
      (node (ref "D15") (pin "2") (pinfunction "IO2_2") (pintype "bidirectional"))
      (node (ref "J7") (pin "9") (pinfunction "9_9") (pintype "passive"))
      (node (ref "J8") (pin "6") (pinfunction "CANL_6") (pintype "bidirectional"))
      (node (ref "U4") (pin "6") (pinfunction "CANL_6") (pintype "bidirectional"))
    )
    (net (code "21") (name "/CAN_P") (class "Default")
      (node (ref "C26") (pin "2") (pinfunction "2_2") (pintype "passive"))
      (node (ref "C28") (pin "2") (pinfunction "2_2") (pintype "passive"))
      (node (ref "CAN ESP BUS") (pin "1") (pinfunction "1_1") (pintype "passive"))
      (node (ref "CAN STM BUS") (pin "1") (pinfunction "1_1") (pintype "passive"))
      (node (ref "D15") (pin "1") (pinfunction "IO1_1") (pintype "bidirectional"))
      (node (ref "J7") (pin "17") (pinfunction "17_17") (pintype "passive"))
      (node (ref "J8") (pin "7") (pinfunction "CANH_7") (pintype "bidirectional"))
      (node (ref "U4") (pin "7") (pinfunction "CANH_7") (pintype "bidirectional"))
    )
    (net (code "22") (name "/CAN_STMF4_RS") (class "Default")
      (node (ref "J8") (pin "8") (pinfunction "RS_8") (pintype "input"))
      (node (ref "R15") (pin "1") (pinfunction "1_1") (pintype "passive"))
    )
    (net (code "23") (name "/ESP_46_Pull-up") (class "Default")
      (node (ref "ESP") (pin "16") (pinfunction "IO46_16") (pintype "bidirectional"))
      (node (ref "R7") (pin "2") (pinfunction "2_2") (pintype "passive"))
    )
    (net (code "24") (name "/ESP_BOOT") (class "Default")
      (node (ref "C18") (pin "1") (pinfunction "1_1") (pintype "passive"))
      (node (ref "ESP") (pin "27") (pinfunction "IO0_27") (pintype "bidirectional"))
      (node (ref "ESP BOOT") (pin "3") (pinfunction "3_3") (pintype "passive"))
      (node (ref "ESP BOOT") (pin "4") (pinfunction "4_4") (pintype "passive"))
    )
    (net (code "25") (name "/ESP_Diode_PWR_K") (class "Default")
      (node (ref "D2") (pin "K") (pinfunction "K_K") (pintype "passive"))
      (node (ref "R2") (pin "1") (pinfunction "1_1") (pintype "passive"))
    )
    (net (code "26") (name "/ESP_LED_RES") (class "Default")
      (node (ref "D8") (pin "K") (pinfunction "K_K") (pintype "passive"))
      (node (ref "R13") (pin "1") (pinfunction "1_1") (pintype "passive"))
    )
    (net (code "28") (name "/ESP_LED_TEST") (class "Default")
      (node (ref "D8") (pin "A") (pinfunction "A_A") (pintype "passive"))
      (node (ref "ESP") (pin "20") (pinfunction "IO12_20") (pintype "bidirectional"))
    )
    (net (code "29") (name "/ESP_RESET") (class "Default")
      (node (ref "C17") (pin "1") (pinfunction "1_1") (pintype "passive"))
      (node (ref "ESP") (pin "3") (pinfunction "EN_3") (pintype "input"))
      (node (ref "ESP RESET") (pin "3") (pinfunction "3_3") (pintype "passive"))
      (node (ref "ESP RESET") (pin "4") (pinfunction "4_4") (pintype "passive"))
      (node (ref "R8") (pin "1") (pinfunction "1_1") (pintype "passive"))
    )
    (net (code "30") (name "/ESP_UART_RX") (class "Default")
      (node (ref "ESP") (pin "36") (pinfunction "RXD0_/_IO44_36") (pintype "bidirectional"))
      (node (ref "UART ESP") (pin "2") (pinfunction "2_2") (pintype "passive"))
    )
    (net (code "31") (name "/ESP_UART_TX") (class "Default")
      (node (ref "ESP") (pin "37") (pinfunction "TXD0_/_IO43_37") (pintype "bidirectional"))
      (node (ref "UART ESP") (pin "1") (pinfunction "1_1") (pintype "passive"))
    )
    (net (code "32") (name "/ESP_USB_D_N") (class "Default")
      (node (ref "D5") (pin "2") (pinfunction "2_2") (pintype "passive"))
      (node (ref "ESP") (pin "13") (pinfunction "USB_D-_/_IO19_13") (pintype "bidirectional"))
      (node (ref "J2") (pin "2") (pinfunction "D-_2") (pintype "bidirectional"))
    )
    (net (code "33") (name "/ESP_USB_D_P") (class "Default")
      (node (ref "D6") (pin "2") (pinfunction "2_2") (pintype "passive"))
      (node (ref "ESP") (pin "14") (pinfunction "USB_D+_/_IO20_14") (pintype "bidirectional"))
      (node (ref "J2") (pin "3") (pinfunction "D+_3") (pintype "bidirectional"))
    )
    (net (code "34") (name "/HDR_AN1_STMF4") (class "Default")
      (node (ref "J7") (pin "20") (pinfunction "20_20") (pintype "passive"))
      (node (ref "STM") (pin "10") (pinfunction "PC2/SPI2_MISO/OTG_HS_ULPI_DIR/FMC_SDNE0/EVENTOUT_10") (pintype "bidirectional"))
    )
    (net (code "35") (name "/HDR_AN2_STMF4") (class "Default")
      (node (ref "J7") (pin "6") (pinfunction "6_6") (pintype "passive"))
      (node (ref "STM") (pin "15") (pinfunction "PA1/TIM2_CH2/TIM5_CH2/USART2_RTS/UART4_RX/QUADSPI_BK1_IO3/SAI2_MCLK_B/EVENTOUT_15") (pintype "bidirectional"))
    )
    (net (code "36") (name "/HDR_AN3_STMF4") (class "Default")
      (node (ref "J7") (pin "31") (pinfunction "31_31") (pintype "passive"))
      (node (ref "STM") (pin "16") (pinfunction "PA2/TIM2_CH3/TIM5_CH3/TIM9_CH1/USART2_TX/SAI2_SCK_B/EVENTOUT_16") (pintype "bidirectional"))
    )
    (net (code "37") (name "/HDR_DI2_STMF4") (class "Default")
      (node (ref "J7") (pin "5") (pinfunction "5_5") (pintype "passive"))
      (node (ref "STM") (pin "11") (pinfunction "PC3/SPI2_MOSI/I2S2_SD/OTG_HS_ULPI_NXT/FMC_SDCKE0/EVENTOUT_11") (pintype "bidirectional"))
    )
    (net (code "38") (name "/HDR_DI3_STMF4") (class "Default")
      (node (ref "J7") (pin "14") (pinfunction "14_14") (pintype "passive"))
      (node (ref "STM") (pin "14") (pinfunction "PA0-WKUP(PA0)TIM2_CH1/TIM2_ETR/TIM5_CH1/TIM8_ETR/USART2_CTS/UART4_TX/EVENTOUT_14") (pintype "bidirectional"))
    )
    (net (code "39") (name "/I2C_SCL") (class "Default")
      (node (ref "GPS_R") (pin "02") (pinfunction "02_02") (pintype "passive"))
      (node (ref "I2C STM BUS") (pin "2") (pinfunction "2_2") (pintype "passive"))
      (node (ref "IMU") (pin "5") (pinfunction "SCL_5") (pintype "passive"))
      (node (ref "STM") (pin "58") (pinfunction "PB6/TIM4_CH1/HDMI_CEC/I2C1_SCL/USART1_TX/CAN2_TX/QUADSPI_BK1_NCS/FMC_SDNE1/DCMI_D5/EVENTOUT_58") (pintype "bidirectional"))
    )
    (net (code "40") (name "/I2C_SDA") (class "Default")
      (node (ref "GPS_R") (pin "03") (pinfunction "03_03") (pintype "passive"))
      (node (ref "I2C STM BUS") (pin "1") (pinfunction "1_1") (pintype "passive"))
      (node (ref "IMU") (pin "4") (pinfunction "SDA_4") (pintype "passive"))
      (node (ref "STM") (pin "59") (pinfunction "PB7/TIM4_CH2/I2C1_SDA/USART1_RX/SPDIFRX_IN0/FMC_NL/DCMI_VSYNC/EVENTOUT_59") (pintype "bidirectional"))
    )
    (net (code "41") (name "/IMU_RST_STMF4") (class "Default")
      (node (ref "IMU") (pin "6") (pinfunction "RST_6") (pintype "passive"))
      (node (ref "STM") (pin "17") (pinfunction "PA3/TIM2_CH4/TIM5_CH4/TIM9_CH2/SAI1_FS_A/USART2_RX/OTG_HS_ULPI_D0/EVENTOUT_17") (pintype "bidirectional"))
    )
    (net (code "42") (name "/PRES1_STMF4") (class "Default")
      (node (ref "J7") (pin "8") (pinfunction "8_8") (pintype "passive"))
      (node (ref "STM") (pin "24") (pinfunction "PC4/I2S1_MCK/SPDIFRX_IN2/FMC_SDNE0/EVENTOUT_24") (pintype "bidirectional"))
    )
    (net (code "43") (name "/PRES2_STMF4") (class "Default")
      (node (ref "J7") (pin "33") (pinfunction "33_33") (pintype "passive"))
      (node (ref "STM") (pin "25") (pinfunction "PC5/USART3_RX/SPDIFRX_IN3/FMC_SDCKE0/EVENTOUT_25") (pintype "bidirectional"))
    )
    (net (code "44") (name "/PROX_ICU1_STMF4") (class "Default")
      (node (ref "J7") (pin "11") (pinfunction "11_11") (pintype "passive"))
      (node (ref "STM") (pin "41") (pinfunction "PA8/MCO1/TIM1_CH1/I2C3_SCL/USART1_CK/OTG_FS_SOF/EVENTOUT_41") (pintype "bidirectional"))
    )
    (net (code "45") (name "/PROX_ICU2_STMF4") (class "Default")
      (node (ref "J7") (pin "2") (pinfunction "2_2") (pintype "passive"))
      (node (ref "STM") (pin "42") (pinfunction "PA9/TIM1_CH2/I2C3_SMBA/SPI2_SCK/I2S2_CK/SAI1_SD_B/USART1_TX/DCMI_D0/EVENTOUT_42") (pintype "bidirectional"))
    )
    (net (code "46") (name "/PROX_ICU3_STMF4") (class "Default")
      (node (ref "J7") (pin "10") (pinfunction "10_10") (pintype "passive"))
      (node (ref "STM") (pin "43") (pinfunction "PA10/TIM1_CH3/USART1_RX/OTG_FS_ID/DCMI_D1/EVENTOUT_43") (pintype "bidirectional"))
    )
    (net (code "47") (name "/PROX_ICU4_STMF4") (class "Default")
      (node (ref "J7") (pin "1") (pinfunction "1_1") (pintype "passive"))
      (node (ref "STM") (pin "44") (pinfunction "PA11/TIM1_CH4/USART1_CTS/CAN1_RX/OTG_FS_DM/EVENTOUT_44") (pintype "bidirectional"))
    )
    (net (code "48") (name "/SD_CLK_ESP") (class "Default")
      (node (ref "ESP") (pin "29") (pinfunction "NC_/_IO36_29") (pintype "bidirectional"))
      (node (ref "J4") (pin "P5") (pinfunction "CLK_P5") (pintype "bidirectional"))
      (node (ref "R22") (pin "2") (pinfunction "2_2") (pintype "passive"))
    )
    (net (code "49") (name "/SD_CMD_ESP") (class "Default")
      (node (ref "ESP") (pin "28") (pinfunction "NC_/_IO35_28") (pintype "bidirectional"))
      (node (ref "J4") (pin "P3") (pinfunction "CMD_P3") (pintype "bidirectional"))
      (node (ref "R20") (pin "1") (pinfunction "1_1") (pintype "passive"))
    )
    (net (code "50") (name "/SD_CardDetection_ESP") (class "Default")
      (node (ref "ESP") (pin "32") (pinfunction "IO39_32") (pintype "bidirectional"))
      (node (ref "J4") (pin "P9") (pinfunction "CD_P9") (pintype "passive"))
      (node (ref "R21") (pin "1") (pinfunction "1_1") (pintype "passive"))
    )
    (net (code "51") (name "/SD_DAT0_ESP") (class "Default")
      (node (ref "ESP") (pin "30") (pinfunction "NC_/_IO37_30") (pintype "bidirectional"))
      (node (ref "J4") (pin "P7") (pinfunction "DAT0_P7") (pintype "bidirectional"))
      (node (ref "R19") (pin "1") (pinfunction "1_1") (pintype "passive"))
    )
    (net (code "52") (name "/SD_DAT1_ESP") (class "Default")
      (node (ref "ESP") (pin "31") (pinfunction "IO38_31") (pintype "bidirectional"))
      (node (ref "J4") (pin "P8") (pinfunction "DAT1_P8") (pintype "bidirectional"))
      (node (ref "R18") (pin "1") (pinfunction "1_1") (pintype "passive"))
    )
    (net (code "53") (name "/SD_DAT2_ESP") (class "Default")
      (node (ref "ESP") (pin "23") (pinfunction "IO21_23") (pintype "bidirectional"))
      (node (ref "J4") (pin "P1") (pinfunction "DAT2_P1") (pintype "bidirectional"))
      (node (ref "R17") (pin "1") (pinfunction "1_1") (pintype "passive"))
    )
    (net (code "54") (name "/SD_DAT3_ESP") (class "Default")
      (node (ref "ESP") (pin "24") (pinfunction "IO47_24") (pintype "bidirectional"))
      (node (ref "J4") (pin "P2") (pinfunction "CD/DAT3_P2") (pintype "bidirectional"))
      (node (ref "R16") (pin "1") (pinfunction "1_1") (pintype "passive"))
    )
    (net (code "55") (name "/SPI_CS") (class "Default")
      (node (ref "ESP") (pin "4") (pinfunction "IO4_4") (pintype "bidirectional"))
      (node (ref "STM") (pin "36") (pinfunction "PB15/RTC_REFIN/TIM1_CH3N/TIM8_CH3N/SPI2_MOSI/I2S2_SD/TIM12_CH2/OTG_HS_DP/EVENTOUT_36") (pintype "bidirectional"))
    )
    (net (code "56") (name "/SPI_MISO") (class "Default")
      (node (ref "ESP") (pin "6") (pinfunction "IO6_6") (pintype "bidirectional"))
      (node (ref "STM") (pin "56") (pinfunction "PB4(NJTRST)/NJTRST/TIM3_CH1/I2C3_SDA/SPI1_MISO/SPI3_MISO/SPI2_NSS/I2S2_WS/EVENTOUT_56") (pintype "bidirectional"))
    )
    (net (code "57") (name "/SPI_MOSI") (class "Default")
      (node (ref "ESP") (pin "7") (pinfunction "IO7_7") (pintype "bidirectional"))
      (node (ref "STM") (pin "57") (pinfunction "PB5/TIM3_CH2/I2C1_SMBA/SPI1_MOSI/I2S1_SD/SPI3_MOSI/I2S3_SD/CAN2_RX/OTG_HS_ULPI_D7/FMC_SDCKE1/DCMI_D10/EVENTOUT_57") (pintype "bidirectional"))
    )
    (net (code "58") (name "/SPI_SCK") (class "Default")
      (node (ref "ESP") (pin "5") (pinfunction "IO5_5") (pintype "bidirectional"))
      (node (ref "STM") (pin "55") (pinfunction "PB3(JTDO/TRACESWO)/JTDO/TRACESWO/TIM2_CH2/I2C2_SDA/SPI1_SCK/I2S1_CK/SPI3_SCK/I2S3_CK/EVENTOUT_55") (pintype "bidirectional"))
    )
    (net (code "59") (name "/STM32F4_BOOT0") (class "Default")
      (node (ref "R5") (pin "2") (pinfunction "2_2") (pintype "passive"))
      (node (ref "STM") (pin "60") (pinfunction "BOOT0_60") (pintype "input"))
    )
    (net (code "60") (name "/STM32F4_Diode_PWR_K") (class "Default")
      (node (ref "D1") (pin "K") (pinfunction "K_K") (pintype "passive"))
      (node (ref "R1") (pin "2") (pinfunction "2_2") (pintype "passive"))
    )
    (net (code "62") (name "/STM32F4_LED_RES") (class "Default")
      (node (ref "D7") (pin "K") (pinfunction "K_K") (pintype "passive"))
      (node (ref "R6") (pin "2") (pinfunction "2_2") (pintype "passive"))
    )
    (net (code "63") (name "/STM32F4_NRST") (class "Default")
      (node (ref "C19") (pin "2") (pinfunction "2_2") (pintype "passive"))
      (node (ref "R10") (pin "1") (pinfunction "1_1") (pintype "passive"))
      (node (ref "STM") (pin "7") (pinfunction "NRST_7") (pintype "bidirectional"))
      (node (ref "STM RESET") (pin "3") (pinfunction "3_3") (pintype "passive"))
      (node (ref "STM RESET") (pin "4") (pinfunction "4_4") (pintype "passive"))
    )
    (net (code "64") (name "/STM32F4_OSC_IN") (class "Default")
      (node (ref "C15") (pin "1") (pinfunction "1_1") (pintype "passive"))
      (node (ref "STM") (pin "5") (pinfunction "PH0-OSC_IN/EVENTOUT_5") (pintype "bidirectional"))
      (node (ref "Y1") (pin "2") (pinfunction "2_2") (pintype "passive"))
    )
    (net (code "65") (name "/STM32F4_OSC_OUT") (class "Default")
      (node (ref "R9") (pin "1") (pinfunction "1_1") (pintype "passive"))
      (node (ref "STM") (pin "6") (pinfunction "PH1-OSC_OUT/EVENTOUT_6") (pintype "bidirectional"))
    )
    (net (code "66") (name "/STM32F4_SWCLK") (class "Default")
      (node (ref "J") (pin "2") (pinfunction "2_2") (pintype "passive"))
      (node (ref "STM") (pin "49") (pinfunction "PA14/JTCK-SWCLK/EVENTOUT_49") (pintype "bidirectional"))
    )
    (net (code "67") (name "/STM32F4_SWDIO") (class "Default")
      (node (ref "J") (pin "4") (pinfunction "4_4") (pintype "passive"))
      (node (ref "STM") (pin "46") (pinfunction "PA13/JTMS-SWDIO/EVENTOUT_46") (pintype "bidirectional"))
    )
    (net (code "68") (name "/STM32F4_VCAP") (class "Default")
      (node (ref "C12") (pin "2") (pinfunction "2_2") (pintype "passive"))
      (node (ref "STM") (pin "30") (pinfunction "VCAP_1_30") (pintype "power_in"))
    )
    (net (code "69") (name "/STM32F4_VCOIN") (class "Default")
      (node (ref "C34") (pin "2") (pinfunction "2_2") (pintype "passive"))
      (node (ref "COIN") (pin "1") (pinfunction "+_1") (pintype "passive"))
      (node (ref "STM") (pin "1") (pinfunction "VBAT_1") (pintype "power_in"))
    )
    (net (code "70") (name "/STMF4_UART2_RX") (class "Default")
      (node (ref "STM") (pin "54") (pinfunction "PD2/TIM3_ETR/UART5_RX/SDIO_CMD/DCMI_D11/EVENTOUT_54") (pintype "bidirectional"))
      (node (ref "UART STM") (pin "2") (pinfunction "2_2") (pintype "passive"))
    )
    (net (code "71") (name "/STMF4_UART2_TX") (class "Default")
      (node (ref "STM") (pin "53") (pinfunction "PC12/I2C2_SDA/SPI3_MOSI/I2S3_SD/USART3_CK/UART5_TX/SDIO_CK/DCMI_D9/EVENTOUT_53") (pintype "bidirectional"))
      (node (ref "UART STM") (pin "1") (pinfunction "1_1") (pintype "passive"))
    )
    (net (code "72") (name "/SUS1_STMF4") (class "Default")
      (node (ref "J7") (pin "12") (pinfunction "12_12") (pintype "passive"))
      (node (ref "STM") (pin "8") (pinfunction "PC0/SAI1_MCLK_B/OTG_HS_ULPI_STP/FMC_SDNWE/EVENTOUT_8") (pintype "bidirectional"))
    )
    (net (code "73") (name "/SUS2_STMF4") (class "Default")
      (node (ref "J7") (pin "4") (pinfunction "4_4") (pintype "passive"))
      (node (ref "STM") (pin "9") (pinfunction "PC1/SPI3_MOSI/I2S3_SD/SAI1_SD_A/SPI2_MOSI/I2S2_SD/EVENTOUT_9") (pintype "bidirectional"))
    )
    (net (code "74") (name "/SUS3_STMF4") (class "Default")
      (node (ref "J7") (pin "7") (pinfunction "7_7") (pintype "passive"))
      (node (ref "STM") (pin "22") (pinfunction "PA6/TIM1_BKIN/TIM3_CH1/TIM8_BKIN/SPI1_MISO/I2S2_MCK/TIM13_CH1/DCMI_PIXCLK/EVENTOUT_22") (pintype "bidirectional"))
    )
    (net (code "75") (name "/SUS4_STMF4") (class "Default")
      (node (ref "J7") (pin "32") (pinfunction "32_32") (pintype "passive"))
      (node (ref "STM") (pin "23") (pinfunction "PA7/TIM1_CH1N/TIM3_CH2/TIM8_CH1N/SPI1_MOSI/I2S1_SD/TIM14_CH1/FMC_SDNWE/EVENTOUT_23") (pintype "bidirectional"))
    )
    (net (code "76") (name "/XTAL_OUT") (class "Default")
      (node (ref "C16") (pin "1") (pinfunction "1_1") (pintype "passive"))
      (node (ref "R9") (pin "2") (pinfunction "2_2") (pintype "passive"))
      (node (ref "Y1") (pin "1") (pinfunction "1_1") (pintype "passive"))
    )
    (net (code "77") (name "CAN_ESP_Vin") (class "Default")
      (node (ref "C20") (pin "2") (pinfunction "2_2") (pintype "passive"))
      (node (ref "C21") (pin "2") (pinfunction "2_2") (pintype "passive"))
      (node (ref "CAN ESP PWR") (pin "2") (pinfunction "2_2") (pintype "passive"))
      (node (ref "U4") (pin "3") (pinfunction "VCC_3") (pintype "power_in"))
    )
    (net (code "78") (name "DC_Fuse_+12V") (class "Default")
      (node (ref "D9") (pin "2") (pinfunction "2_2") (pintype "passive"))
      (node (ref "F1") (pin "2") (pinfunction "2_2") (pintype "passive"))
      (node (ref "Q2") (pin "2") (pinfunction "D_2") (pintype "passive"))
    )
    (net (code "79") (name "DC_IN_+12V") (class "Default")
      (node (ref "F1") (pin "1") (pinfunction "1_1") (pintype "passive"))
      (node (ref "J11") (pin "2") (pinfunction "2_2") (pintype "passive"))
      (node (ref "J7") (pin "34") (pinfunction "34_34") (pintype "passive"))
    )
    (net (code "80") (name "GND") (class "Default")
      (node (ref "C1") (pin "1") (pinfunction "1_1") (pintype "passive"))
      (node (ref "C10") (pin "1") (pinfunction "1_1") (pintype "passive"))
      (node (ref "C11") (pin "1") (pinfunction "1_1") (pintype "passive"))
      (node (ref "C12") (pin "1") (pinfunction "1_1") (pintype "passive"))
      (node (ref "C13") (pin "2") (pinfunction "2_2") (pintype "passive"))
      (node (ref "C14") (pin "2") (pinfunction "2_2") (pintype "passive"))
      (node (ref "C15") (pin "2") (pinfunction "2_2") (pintype "passive"))
      (node (ref "C16") (pin "2") (pinfunction "2_2") (pintype "passive"))
      (node (ref "C17") (pin "2") (pinfunction "2_2") (pintype "passive"))
      (node (ref "C18") (pin "2") (pinfunction "2_2") (pintype "passive"))
      (node (ref "C19") (pin "1") (pinfunction "1_1") (pintype "passive"))
      (node (ref "C2") (pin "1") (pinfunction "1_1") (pintype "passive"))
      (node (ref "C20") (pin "1") (pinfunction "1_1") (pintype "passive"))
      (node (ref "C21") (pin "1") (pinfunction "1_1") (pintype "passive"))
      (node (ref "C22") (pin "1") (pinfunction "1_1") (pintype "passive"))
      (node (ref "C23") (pin "1") (pinfunction "1_1") (pintype "passive"))
      (node (ref "C24") (pin "1") (pinfunction "1_1") (pintype "passive"))
      (node (ref "C25") (pin "1") (pinfunction "1_1") (pintype "passive"))
      (node (ref "C26") (pin "1") (pinfunction "1_1") (pintype "passive"))
      (node (ref "C27") (pin "1") (pinfunction "1_1") (pintype "passive"))
      (node (ref "C28") (pin "1") (pinfunction "1_1") (pintype "passive"))
      (node (ref "C29") (pin "1") (pinfunction "1_1") (pintype "passive"))
      (node (ref "C3") (pin "1") (pinfunction "1_1") (pintype "passive"))
      (node (ref "C30") (pin "2") (pinfunction "2_2") (pintype "passive"))
      (node (ref "C31") (pin "2") (pinfunction "2_2") (pintype "passive"))
      (node (ref "C32") (pin "1") (pinfunction "1_1") (pintype "passive"))
      (node (ref "C33") (pin "1") (pinfunction "1_1") (pintype "passive"))
      (node (ref "C34") (pin "1") (pinfunction "1_1") (pintype "passive"))
      (node (ref "C4") (pin "1") (pinfunction "1_1") (pintype "passive"))
      (node (ref "C6") (pin "1") (pinfunction "1_1") (pintype "passive"))
      (node (ref "C7") (pin "1") (pinfunction "1_1") (pintype "passive"))
      (node (ref "C8") (pin "1") (pinfunction "1_1") (pintype "passive"))
      (node (ref "C9") (pin "1") (pinfunction "1_1") (pintype "passive"))
      (node (ref "CAN ESP BUS") (pin "3") (pinfunction "3_3") (pintype "passive"))
      (node (ref "CAN STM BUS") (pin "3") (pinfunction "3_3") (pintype "passive"))
      (node (ref "COIN") (pin "2") (pinfunction "-_2") (pintype "passive"))
      (node (ref "D10") (pin "A") (pinfunction "A_A") (pintype "passive"))
      (node (ref "D11") (pin "K") (pinfunction "K_K") (pintype "passive"))
      (node (ref "D14") (pin "K") (pinfunction "K_K") (pintype "passive"))
      (node (ref "D15") (pin "3") (pinfunction "GND_3") (pintype "power_in"))
      (node (ref "D3") (pin "1") (pinfunction "1_1") (pintype "passive"))
      (node (ref "D4") (pin "1") (pinfunction "1_1") (pintype "passive"))
      (node (ref "D5") (pin "1") (pinfunction "1_1") (pintype "passive"))
      (node (ref "D6") (pin "1") (pinfunction "1_1") (pintype "passive"))
      (node (ref "D9") (pin "1") (pinfunction "1_1") (pintype "passive"))
      (node (ref "ESP") (pin "1") (pinfunction "GND_1") (pintype "power_in"))
      (node (ref "ESP") (pin "40") (pinfunction "GND_40") (pintype "power_in"))
      (node (ref "ESP") (pin "41_1") (pinfunction "GND_41_1") (pintype "power_in"))
      (node (ref "ESP") (pin "41_2") (pinfunction "GND_41_2") (pintype "power_in"))
      (node (ref "ESP") (pin "41_3") (pinfunction "GND_41_3") (pintype "power_in"))
      (node (ref "ESP") (pin "41_4") (pinfunction "GND_41_4") (pintype "power_in"))
      (node (ref "ESP") (pin "41_5") (pinfunction "GND_41_5") (pintype "power_in"))
      (node (ref "ESP") (pin "41_6") (pinfunction "GND_41_6") (pintype "power_in"))
      (node (ref "ESP") (pin "41_7") (pinfunction "GND_41_7") (pintype "power_in"))
      (node (ref "ESP") (pin "41_8") (pinfunction "GND_41_8") (pintype "power_in"))
      (node (ref "ESP") (pin "41_9") (pinfunction "GND_41_9") (pintype "power_in"))
      (node (ref "ESP BOOT") (pin "1") (pinfunction "1_1") (pintype "passive"))
      (node (ref "ESP BOOT") (pin "2") (pinfunction "2_2") (pintype "passive"))
      (node (ref "ESP RESET") (pin "1") (pinfunction "1_1") (pintype "passive"))
      (node (ref "ESP RESET") (pin "2") (pinfunction "2_2") (pintype "passive"))
      (node (ref "GPS_L") (pin "07") (pinfunction "07_07") (pintype "passive"))
      (node (ref "GPS_R") (pin "05") (pinfunction "05_05") (pintype "passive"))
      (node (ref "I2C STM BUS") (pin "3") (pinfunction "3_3") (pintype "passive"))
      (node (ref "IMU") (pin "3") (pinfunction "GND_3") (pintype "passive"))
      (node (ref "IMU") (pin "7") (pinfunction "ADR_7") (pintype "passive"))
      (node (ref "J") (pin "5") (pinfunction "5_5") (pintype "passive"))
      (node (ref "J") (pin "6") (pinfunction "6_6") (pintype "passive"))
      (node (ref "J11") (pin "1") (pinfunction "1_1") (pintype "passive"))
      (node (ref "J11") (pin "3") (pinfunction "3_3") (pintype "passive"))
      (node (ref "J2") (pin "4") (pinfunction "GND_4") (pintype "power_in"))
      (node (ref "J2") (pin "S1") (pinfunction "SHIELD_S1") (pintype "passive"))
      (node (ref "J2") (pin "S2") (pinfunction "SHIELD_S2") (pintype "passive"))
      (node (ref "J4") (pin "P6") (pinfunction "VSS_P6") (pintype "power_in"))
      (node (ref "J4") (pin "SH1") (pinfunction "SHIELD_SH1") (pintype "power_in"))
      (node (ref "J4") (pin "SH2") (pinfunction "SHIELD_SH2") (pintype "power_in"))
      (node (ref "J4") (pin "SH3") (pinfunction "SHIELD_SH3") (pintype "power_in"))
      (node (ref "J4") (pin "SH4") (pinfunction "SHIELD_SH4") (pintype "power_in"))
      (node (ref "J7") (pin "13") (pinfunction "13_13") (pintype "passive"))
      (node (ref "J7") (pin "15") (pinfunction "15_15") (pintype "passive"))
      (node (ref "J7") (pin "16") (pinfunction "16_16") (pintype "passive"))
      (node (ref "J7") (pin "18") (pinfunction "18_18") (pintype "passive"))
      (node (ref "J7") (pin "24") (pinfunction "24_24") (pintype "passive"))
      (node (ref "J7") (pin "25") (pinfunction "25_25") (pintype "passive"))
      (node (ref "J7") (pin "3") (pinfunction "3_3") (pintype "passive"))
      (node (ref "J8") (pin "2") (pinfunction "VSS_2") (pintype "power_in"))
      (node (ref "Q2") (pin "1") (pinfunction "G_1") (pintype "passive"))
      (node (ref "R1") (pin "1") (pinfunction "1_1") (pintype "passive"))
      (node (ref "R13") (pin "2") (pinfunction "2_2") (pintype "passive"))
      (node (ref "R15") (pin "2") (pinfunction "2_2") (pintype "passive"))
      (node (ref "R2") (pin "2") (pinfunction "2_2") (pintype "passive"))
      (node (ref "R22") (pin "1") (pinfunction "1_1") (pintype "passive"))
      (node (ref "R23") (pin "1") (pinfunction "1_1") (pintype "passive"))
      (node (ref "R3") (pin "2") (pinfunction "2_2") (pintype "passive"))
      (node (ref "R5") (pin "1") (pinfunction "1_1") (pintype "passive"))
      (node (ref "R6") (pin "1") (pinfunction "1_1") (pintype "passive"))
      (node (ref "STM") (pin "12") (pinfunction "VSSA/VREF-_12") (pintype "power_in"))
      (node (ref "STM") (pin "18") (pinfunction "VSS_18") (pintype "power_in"))
      (node (ref "STM") (pin "31") (pinfunction "VSS_31") (pintype "power_in"))
      (node (ref "STM") (pin "47") (pinfunction "VSS_47") (pintype "power_in"))
      (node (ref "STM") (pin "63") (pinfunction "VSS_63") (pintype "power_in"))
      (node (ref "STM RESET") (pin "1") (pinfunction "1_1") (pintype "passive"))
      (node (ref "STM RESET") (pin "2") (pinfunction "2_2") (pintype "passive"))
      (node (ref "U1") (pin "1") (pinfunction "GND/ADJ_1") (pintype "power_in"))
      (node (ref "U2") (pin "1") (pinfunction "GND/ADJ_1") (pintype "power_in"))
      (node (ref "U4") (pin "2") (pinfunction "GND_2") (pintype "power_in"))
      (node (ref "U5") (pin "3") (pinfunction "GND_3") (pintype "power_in"))
      (node (ref "U5") (pin "5") (pinfunction "~{ON}/OFF_5") (pintype "input"))
      (node (ref "U5") (pin "6") (pinfunction "GND_6") (pintype "power_in"))
      (node (ref "UART ESP") (pin "3") (pinfunction "3_3") (pintype "passive"))
      (node (ref "UART STM") (pin "3") (pinfunction "3_3") (pintype "passive"))
    )
    (net (code "81") (name "Net-(STM-PB14{slash}TIM1_CH2N{slash}TIM8_CH2N{slash}SPI2_MISO{slash}USART3_RTS{slash}TIM12_CH1{slash}OTG_HS_DM{slash}EVENTOUT)") (class "Default")
      (node (ref "D7") (pin "A") (pinfunction "A_A") (pintype "passive"))
      (node (ref "STM") (pin "35") (pinfunction "PB14/TIM1_CH2N/TIM8_CH2N/SPI2_MISO/USART3_RTS/TIM12_CH1/OTG_HS_DM/EVENTOUT_35") (pintype "bidirectional"))
    )
    (net (code "82") (name "unconnected-(ESP-IO1-Pad39)") (class "Default")
      (node (ref "ESP") (pin "39") (pinfunction "IO1_39") (pintype "bidirectional"))
    )
    (net (code "83") (name "unconnected-(ESP-IO2-Pad38)") (class "Default")
      (node (ref "ESP") (pin "38") (pinfunction "IO2_38") (pintype "bidirectional"))
    )
    (net (code "84") (name "unconnected-(ESP-IO3-Pad15)") (class "Default")
      (node (ref "ESP") (pin "15") (pinfunction "IO3_15") (pintype "bidirectional"))
    )
    (net (code "85") (name "unconnected-(ESP-IO8-Pad12)") (class "Default")
      (node (ref "ESP") (pin "12") (pinfunction "IO8_12") (pintype "bidirectional"))
    )
    (net (code "86") (name "unconnected-(ESP-IO9-Pad17)") (class "Default")
      (node (ref "ESP") (pin "17") (pinfunction "IO9_17") (pintype "bidirectional"))
    )
    (net (code "87") (name "unconnected-(ESP-IO10-Pad18)") (class "Default")
      (node (ref "ESP") (pin "18") (pinfunction "IO10_18") (pintype "bidirectional"))
    )
    (net (code "88") (name "unconnected-(ESP-IO11-Pad19)") (class "Default")
      (node (ref "ESP") (pin "19") (pinfunction "IO11_19") (pintype "bidirectional"))
    )
    (net (code "89") (name "unconnected-(ESP-IO15-Pad8)") (class "Default")
      (node (ref "ESP") (pin "8") (pinfunction "IO15_8") (pintype "bidirectional"))
    )
    (net (code "90") (name "unconnected-(ESP-IO16-Pad9)") (class "Default")
      (node (ref "ESP") (pin "9") (pinfunction "IO16_9") (pintype "bidirectional"))
    )
    (net (code "91") (name "unconnected-(ESP-IO40-Pad33)") (class "Default")
      (node (ref "ESP") (pin "33") (pinfunction "IO40_33") (pintype "bidirectional"))
    )
    (net (code "92") (name "unconnected-(ESP-IO41-Pad34)") (class "Default")
      (node (ref "ESP") (pin "34") (pinfunction "IO41_34") (pintype "bidirectional"))
    )
    (net (code "93") (name "unconnected-(ESP-IO42-Pad35)") (class "Default")
      (node (ref "ESP") (pin "35") (pinfunction "IO42_35") (pintype "bidirectional"))
    )
    (net (code "94") (name "unconnected-(ESP-IO45-Pad26)") (class "Default")
      (node (ref "ESP") (pin "26") (pinfunction "IO45_26") (pintype "bidirectional"))
    )
    (net (code "95") (name "unconnected-(ESP-IO48-Pad25)") (class "Default")
      (node (ref "ESP") (pin "25") (pinfunction "IO48_25") (pintype "bidirectional"))
    )
    (net (code "96") (name "unconnected-(ESP-RXD1_{slash}_IO18-Pad11)") (class "Default")
      (node (ref "ESP") (pin "11") (pinfunction "RXD1_/_IO18_11") (pintype "bidirectional"))
    )
    (net (code "97") (name "unconnected-(ESP-TXD1_{slash}_IO17-Pad10)") (class "Default")
      (node (ref "ESP") (pin "10") (pinfunction "TXD1_/_IO17_10") (pintype "bidirectional"))
    )
    (net (code "98") (name "unconnected-(GPS_L-Pad01)") (class "Default")
      (node (ref "GPS_L") (pin "01") (pinfunction "01_01") (pintype "passive"))
    )
    (net (code "99") (name "unconnected-(GPS_L-Pad02)") (class "Default")
      (node (ref "GPS_L") (pin "02") (pinfunction "02_02") (pintype "passive"))
    )
    (net (code "100") (name "unconnected-(GPS_L-Pad03)") (class "Default")
      (node (ref "GPS_L") (pin "03") (pinfunction "03_03") (pintype "passive"))
    )
    (net (code "101") (name "unconnected-(GPS_L-Pad04)") (class "Default")
      (node (ref "GPS_L") (pin "04") (pinfunction "04_04") (pintype "passive"))
    )
    (net (code "102") (name "unconnected-(GPS_L-Pad06)") (class "Default")
      (node (ref "GPS_L") (pin "06") (pinfunction "06_06") (pintype "passive"))
    )
    (net (code "103") (name "unconnected-(GPS_L-Pad08)") (class "Default")
      (node (ref "GPS_L") (pin "08") (pinfunction "08_08") (pintype "passive"))
    )
    (net (code "104") (name "unconnected-(GPS_L-Pad09)") (class "Default")
      (node (ref "GPS_L") (pin "09") (pinfunction "09_09") (pintype "passive"))
    )
    (net (code "105") (name "unconnected-(GPS_L-Pad10)") (class "Default")
      (node (ref "GPS_L") (pin "10") (pinfunction "10_10") (pintype "passive"))
    )
    (net (code "106") (name "unconnected-(GPS_L-Pad11)") (class "Default")
      (node (ref "GPS_L") (pin "11") (pinfunction "11_11") (pintype "passive"))
    )
    (net (code "107") (name "unconnected-(GPS_R-Pad01)") (class "Default")
      (node (ref "GPS_R") (pin "01") (pinfunction "01_01") (pintype "passive"))
    )
    (net (code "108") (name "unconnected-(GPS_R-Pad06)") (class "Default")
      (node (ref "GPS_R") (pin "06") (pinfunction "06_06") (pintype "passive"))
    )
    (net (code "109") (name "unconnected-(GPS_R-Pad07)") (class "Default")
      (node (ref "GPS_R") (pin "07") (pinfunction "07_07") (pintype "passive"))
    )
    (net (code "110") (name "unconnected-(GPS_R-Pad08)") (class "Default")
      (node (ref "GPS_R") (pin "08") (pinfunction "08_08") (pintype "passive"))
    )
    (net (code "111") (name "unconnected-(GPS_R-Pad09)") (class "Default")
      (node (ref "GPS_R") (pin "09") (pinfunction "09_09") (pintype "passive"))
    )
    (net (code "112") (name "unconnected-(GPS_R-Pad10)") (class "Default")
      (node (ref "GPS_R") (pin "10") (pinfunction "10_10") (pintype "passive"))
    )
    (net (code "113") (name "unconnected-(GPS_R-Pad11)") (class "Default")
      (node (ref "GPS_R") (pin "11") (pinfunction "11_11") (pintype "passive"))
    )
    (net (code "114") (name "unconnected-(IMU-INT-Pad8)") (class "Default")
      (node (ref "IMU") (pin "8") (pinfunction "INT_8") (pintype "passive+no_connect"))
    )
    (net (code "115") (name "unconnected-(IMU-PS0-Pad10)") (class "Default")
      (node (ref "IMU") (pin "10") (pinfunction "PS0_10") (pintype "passive+no_connect"))
    )
    (net (code "116") (name "unconnected-(IMU-PS1-Pad9)") (class "Default")
      (node (ref "IMU") (pin "9") (pinfunction "PS1_9") (pintype "passive+no_connect"))
    )
    (net (code "117") (name "unconnected-(IMU-Vin-Pad1)") (class "Default")
      (node (ref "IMU") (pin "1") (pinfunction "Vin_1") (pintype "passive"))
    )
    (net (code "118") (name "unconnected-(J-Pad1)") (class "Default")
      (node (ref "J") (pin "1") (pinfunction "1_1") (pintype "passive+no_connect"))
    )
    (net (code "119") (name "unconnected-(J-Pad3)") (class "Default")
      (node (ref "J") (pin "3") (pinfunction "3_3") (pintype "passive+no_connect"))
    )
    (net (code "120") (name "unconnected-(J-Pad7)") (class "Default")
      (node (ref "J") (pin "7") (pinfunction "7_7") (pintype "passive+no_connect"))
    )
    (net (code "121") (name "unconnected-(J-Pad8)") (class "Default")
      (node (ref "J") (pin "8") (pinfunction "8_8") (pintype "passive+no_connect"))
    )
    (net (code "122") (name "unconnected-(J7-Pad19)") (class "Default")
      (node (ref "J7") (pin "19") (pinfunction "19_19") (pintype "passive+no_connect"))
    )
    (net (code "123") (name "unconnected-(J7-Pad26)") (class "Default")
      (node (ref "J7") (pin "26") (pinfunction "26_26") (pintype "passive+no_connect"))
    )
    (net (code "124") (name "unconnected-(J7-Pad27)") (class "Default")
      (node (ref "J7") (pin "27") (pinfunction "27_27") (pintype "passive+no_connect"))
    )
    (net (code "125") (name "unconnected-(J8-VREF-Pad5)") (class "Default")
      (node (ref "J8") (pin "5") (pinfunction "VREF_5") (pintype "output+no_connect"))
    )
    (net (code "126") (name "unconnected-(STM-PA4{slash}SPI1_NSS{slash}I2S1_WS{slash}SPI3_NSS{slash}I2S3_WS{slash}USART2_CK{slash}OTG_HS_SOF{slash}DCMI_HSYNC{slash}EVENTOUT-Pad20)") (class "Default")
      (node (ref "STM") (pin "20") (pinfunction "PA4/SPI1_NSS/I2S1_WS/SPI3_NSS/I2S3_WS/USART2_CK/OTG_HS_SOF/DCMI_HSYNC/EVENTOUT_20") (pintype "bidirectional"))
    )
    (net (code "127") (name "unconnected-(STM-PA5{slash}TIM2_CH1{slash}TIM2_ETR{slash}TIM8_CH1N{slash}SPI1_SCK{slash}I2S1_CK{slash}OTG_HS_ULPI_CK{slash}EVENTOUT-Pad21)") (class "Default")
      (node (ref "STM") (pin "21") (pinfunction "PA5/TIM2_CH1/TIM2_ETR/TIM8_CH1N/SPI1_SCK/I2S1_CK/OTG_HS_ULPI_CK/EVENTOUT_21") (pintype "bidirectional"))
    )
    (net (code "128") (name "unconnected-(STM-PA12{slash}TIM1_ETR{slash}USART1_RTS{slash}SAI2_FS_B{slash}CAN1_TX{slash}OTG_FS_DP{slash}EVENTOUT-Pad45)") (class "Default")
      (node (ref "STM") (pin "45") (pinfunction "PA12/TIM1_ETR/USART1_RTS/SAI2_FS_B/CAN1_TX/OTG_FS_DP/EVENTOUT_45") (pintype "bidirectional"))
    )
    (net (code "129") (name "unconnected-(STM-PA15{slash}JTDI{slash}TIM2_CH1{slash}TIM2_ETR{slash}HDMI_CEC{slash}SPI1_NSS{slash}I2S1_WS{slash}SPI3_NSS{slash}I2S3_WS{slash}UART4_RTS{slash}EVENTOUT-Pad50)") (class "Default")
      (node (ref "STM") (pin "50") (pinfunction "PA15/JTDI/TIM2_CH1/TIM2_ETR/HDMI_CEC/SPI1_NSS/I2S1_WS/SPI3_NSS/I2S3_WS/UART4_RTS/EVENTOUT_50") (pintype "bidirectional"))
    )
    (net (code "130") (name "unconnected-(STM-PB0{slash}TIM1_CH2N{slash}TIM3_CH3{slash}TIM8_CH2N{slash}SPI3_MOSI{slash}I2S3_SD{slash}UART4_CTS{slash}OTG_HS_ULPI_D1{slash}SDIO_D1{slash}EVENTOUT-Pad26)") (class "Default")
      (node (ref "STM") (pin "26") (pinfunction "PB0/TIM1_CH2N/TIM3_CH3/TIM8_CH2N/SPI3_MOSI/I2S3_SD/UART4_CTS/OTG_HS_ULPI_D1/SDIO_D1/EVENTOUT_26") (pintype "bidirectional"))
    )
    (net (code "131") (name "unconnected-(STM-PB1{slash}TIM1_CH3N{slash}TIM3_CH4{slash}TIM8_CH3N{slash}OTG_HS_ULPI_D2{slash}SDIO_D2{slash}EVENTOUT-Pad27)") (class "Default")
      (node (ref "STM") (pin "27") (pinfunction "PB1/TIM1_CH3N/TIM3_CH4/TIM8_CH3N/OTG_HS_ULPI_D2/SDIO_D2/EVENTOUT_27") (pintype "bidirectional"))
    )
    (net (code "132") (name "unconnected-(STM-PB2-BOOT1(PB2){slash}TIM2_CH4{slash}SAI1_SD_A{slash}SPI3_MOSI{slash}I2S3_SD{slash}QUADSPI_CLK{slash}OTG_HS_ULPI_D4{slash}SDIO_CK{slash}EVENTOUT-Pad28)") (class "Default")
      (node (ref "STM") (pin "28") (pinfunction "PB2-BOOT1(PB2)/TIM2_CH4/SAI1_SD_A/SPI3_MOSI/I2S3_SD/QUADSPI_CLK/OTG_HS_ULPI_D4/SDIO_CK/EVENTOUT_28") (pintype "bidirectional"))
    )
    (net (code "133") (name "unconnected-(STM-PB10{slash}TIM2_CH3{slash}I2C2_SCL{slash}SPI2_SCK{slash}I2S2_CK{slash}SAI1_SCK_A{slash}USART3_TX{slash}OTG_HS_ULPI_D3{slash}EVENTOUT-Pad29)") (class "Default")
      (node (ref "STM") (pin "29") (pinfunction "PB10/TIM2_CH3/I2C2_SCL/SPI2_SCK/I2S2_CK/SAI1_SCK_A/USART3_TX/OTG_HS_ULPI_D3/EVENTOUT_29") (pintype "bidirectional"))
    )
    (net (code "134") (name "unconnected-(STM-PB12{slash}TIM1_BKIN{slash}I2C2_SMBA{slash}SPI2_NSS{slash}I2S2_WS{slash}SAI1_SCK_B{slash}USART3_CK{slash}CAN2_RX{slash}OTG_HS_ULPI_D5{slash}OTG_HS_ID{slash}EVENTOUT-Pad33)") (class "Default")
      (node (ref "STM") (pin "33") (pinfunction "PB12/TIM1_BKIN/I2C2_SMBA/SPI2_NSS/I2S2_WS/SAI1_SCK_B/USART3_CK/CAN2_RX/OTG_HS_ULPI_D5/OTG_HS_ID/EVENTOUT_33") (pintype "bidirectional"))
    )
    (net (code "135") (name "unconnected-(STM-PB13{slash}TIM1_CH1N{slash}SPI2_SCK{slash}I2S2_CK{slash}USART3_CTS{slash}CAN2_TX{slash}OTG_HS_ULPI_D6{slash}EVENTOUT-Pad34)") (class "Default")
      (node (ref "STM") (pin "34") (pinfunction "PB13/TIM1_CH1N/SPI2_SCK/I2S2_CK/USART3_CTS/CAN2_TX/OTG_HS_ULPI_D6/EVENTOUT_34") (pintype "bidirectional"))
    )
    (net (code "136") (name "unconnected-(STM-PC6{slash}TIM3_CH1{slash}TIM8_CH1{slash}FMPI2C1_SCL{slash}I2S2_MCK{slash}USART6_TX{slash}SDIO_D6{slash}DCMI_D0{slash}EVENTOUT-Pad37)") (class "Default")
      (node (ref "STM") (pin "37") (pinfunction "PC6/TIM3_CH1/TIM8_CH1/FMPI2C1_SCL/I2S2_MCK/USART6_TX/SDIO_D6/DCMI_D0/EVENTOUT_37") (pintype "bidirectional"))
    )
    (net (code "137") (name "unconnected-(STM-PC7{slash}TIM3_CH2{slash}TIM8_CH2{slash}FMPI2C1_SDA{slash}SPI2_SCK{slash}I2S2_CK{slash}I2S3_MCK{slash}SPDIFRX_IN1{slash}USART6_RX{slash}SDIO_D7{slash}DCMI_D1{slash}EVENTOUT-Pad38)") (class "Default")
      (node (ref "STM") (pin "38") (pinfunction "PC7/TIM3_CH2/TIM8_CH2/FMPI2C1_SDA/SPI2_SCK/I2S2_CK/I2S3_MCK/SPDIFRX_IN1/USART6_RX/SDIO_D7/DCMI_D1/EVENTOUT_38") (pintype "bidirectional"))
    )
    (net (code "138") (name "unconnected-(STM-PC8{slash}TRACED0{slash}TIM3_CH3{slash}TIM8_CH3{slash}UART5_RTS{slash}USART6_CK{slash}SDIO_D0{slash}DCMI_D2{slash}EVENTOUT-Pad39)") (class "Default")
      (node (ref "STM") (pin "39") (pinfunction "PC8/TRACED0/TIM3_CH3/TIM8_CH3/UART5_RTS/USART6_CK/SDIO_D0/DCMI_D2/EVENTOUT_39") (pintype "bidirectional"))
    )
    (net (code "139") (name "unconnected-(STM-PC9{slash}MCO2{slash}TIM3_CH4{slash}TIM8_CH4{slash}I2C3_SDA{slash}I2S_CKIN{slash}UART5_CTS{slash}QUADSPI_BK1_IO0{slash}SDIO_D1{slash}DCMI_D3{slash}EVENTOUT-Pad40)") (class "Default")
      (node (ref "STM") (pin "40") (pinfunction "PC9/MCO2/TIM3_CH4/TIM8_CH4/I2C3_SDA/I2S_CKIN/UART5_CTS/QUADSPI_BK1_IO0/SDIO_D1/DCMI_D3/EVENTOUT_40") (pintype "bidirectional"))
    )
    (net (code "140") (name "unconnected-(STM-PC10{slash}SPI3_SCK{slash}I2S3_CK{slash}USART3_TX{slash}UART4_TX{slash}QUADSPI_BK1_IO1{slash}SDIO_D2{slash}DCMI_D8{slash}EVENTOUT-Pad51)") (class "Default")
      (node (ref "STM") (pin "51") (pinfunction "PC10/SPI3_SCK/I2S3_CK/USART3_TX/UART4_TX/QUADSPI_BK1_IO1/SDIO_D2/DCMI_D8/EVENTOUT_51") (pintype "bidirectional"))
    )
    (net (code "141") (name "unconnected-(STM-PC11{slash}SPI3_MISO{slash}USART3_RX{slash}UART4_RX{slash}QUADSPI_BK2_NCS{slash}SDIO_D3{slash}DCMI_D4{slash}EVENTOUT-Pad52)") (class "Default")
      (node (ref "STM") (pin "52") (pinfunction "PC11/SPI3_MISO/USART3_RX/UART4_RX/QUADSPI_BK2_NCS/SDIO_D3/DCMI_D4/EVENTOUT_52") (pintype "bidirectional"))
    )
    (net (code "142") (name "unconnected-(STM-PC13{slash}EVENTOUT-Pad2)") (class "Default")
      (node (ref "STM") (pin "2") (pinfunction "PC13/EVENTOUT_2") (pintype "bidirectional"))
    )
    (net (code "143") (name "unconnected-(STM-PC14-OSC32_IN(PC14){slash}EVENTOUT-Pad3)") (class "Default")
      (node (ref "STM") (pin "3") (pinfunction "PC14-OSC32_IN(PC14)/EVENTOUT_3") (pintype "bidirectional"))
    )
    (net (code "144") (name "unconnected-(STM-PC15-OSC32_OUT(PC15){slash}EVENTOUT-Pad4)") (class "Default")
      (node (ref "STM") (pin "4") (pinfunction "PC15-OSC32_OUT(PC15)/EVENTOUT_4") (pintype "bidirectional"))
    )
    (net (code "145") (name "unconnected-(U4-VREF-Pad5)") (class "Default")
      (node (ref "U4") (pin "5") (pinfunction "VREF_5") (pintype "input+no_connect"))
    )
  )
)
